# ASCII_10_FPGA_misc.net
KiCad netlist of a schematic drawn in Altium Designer
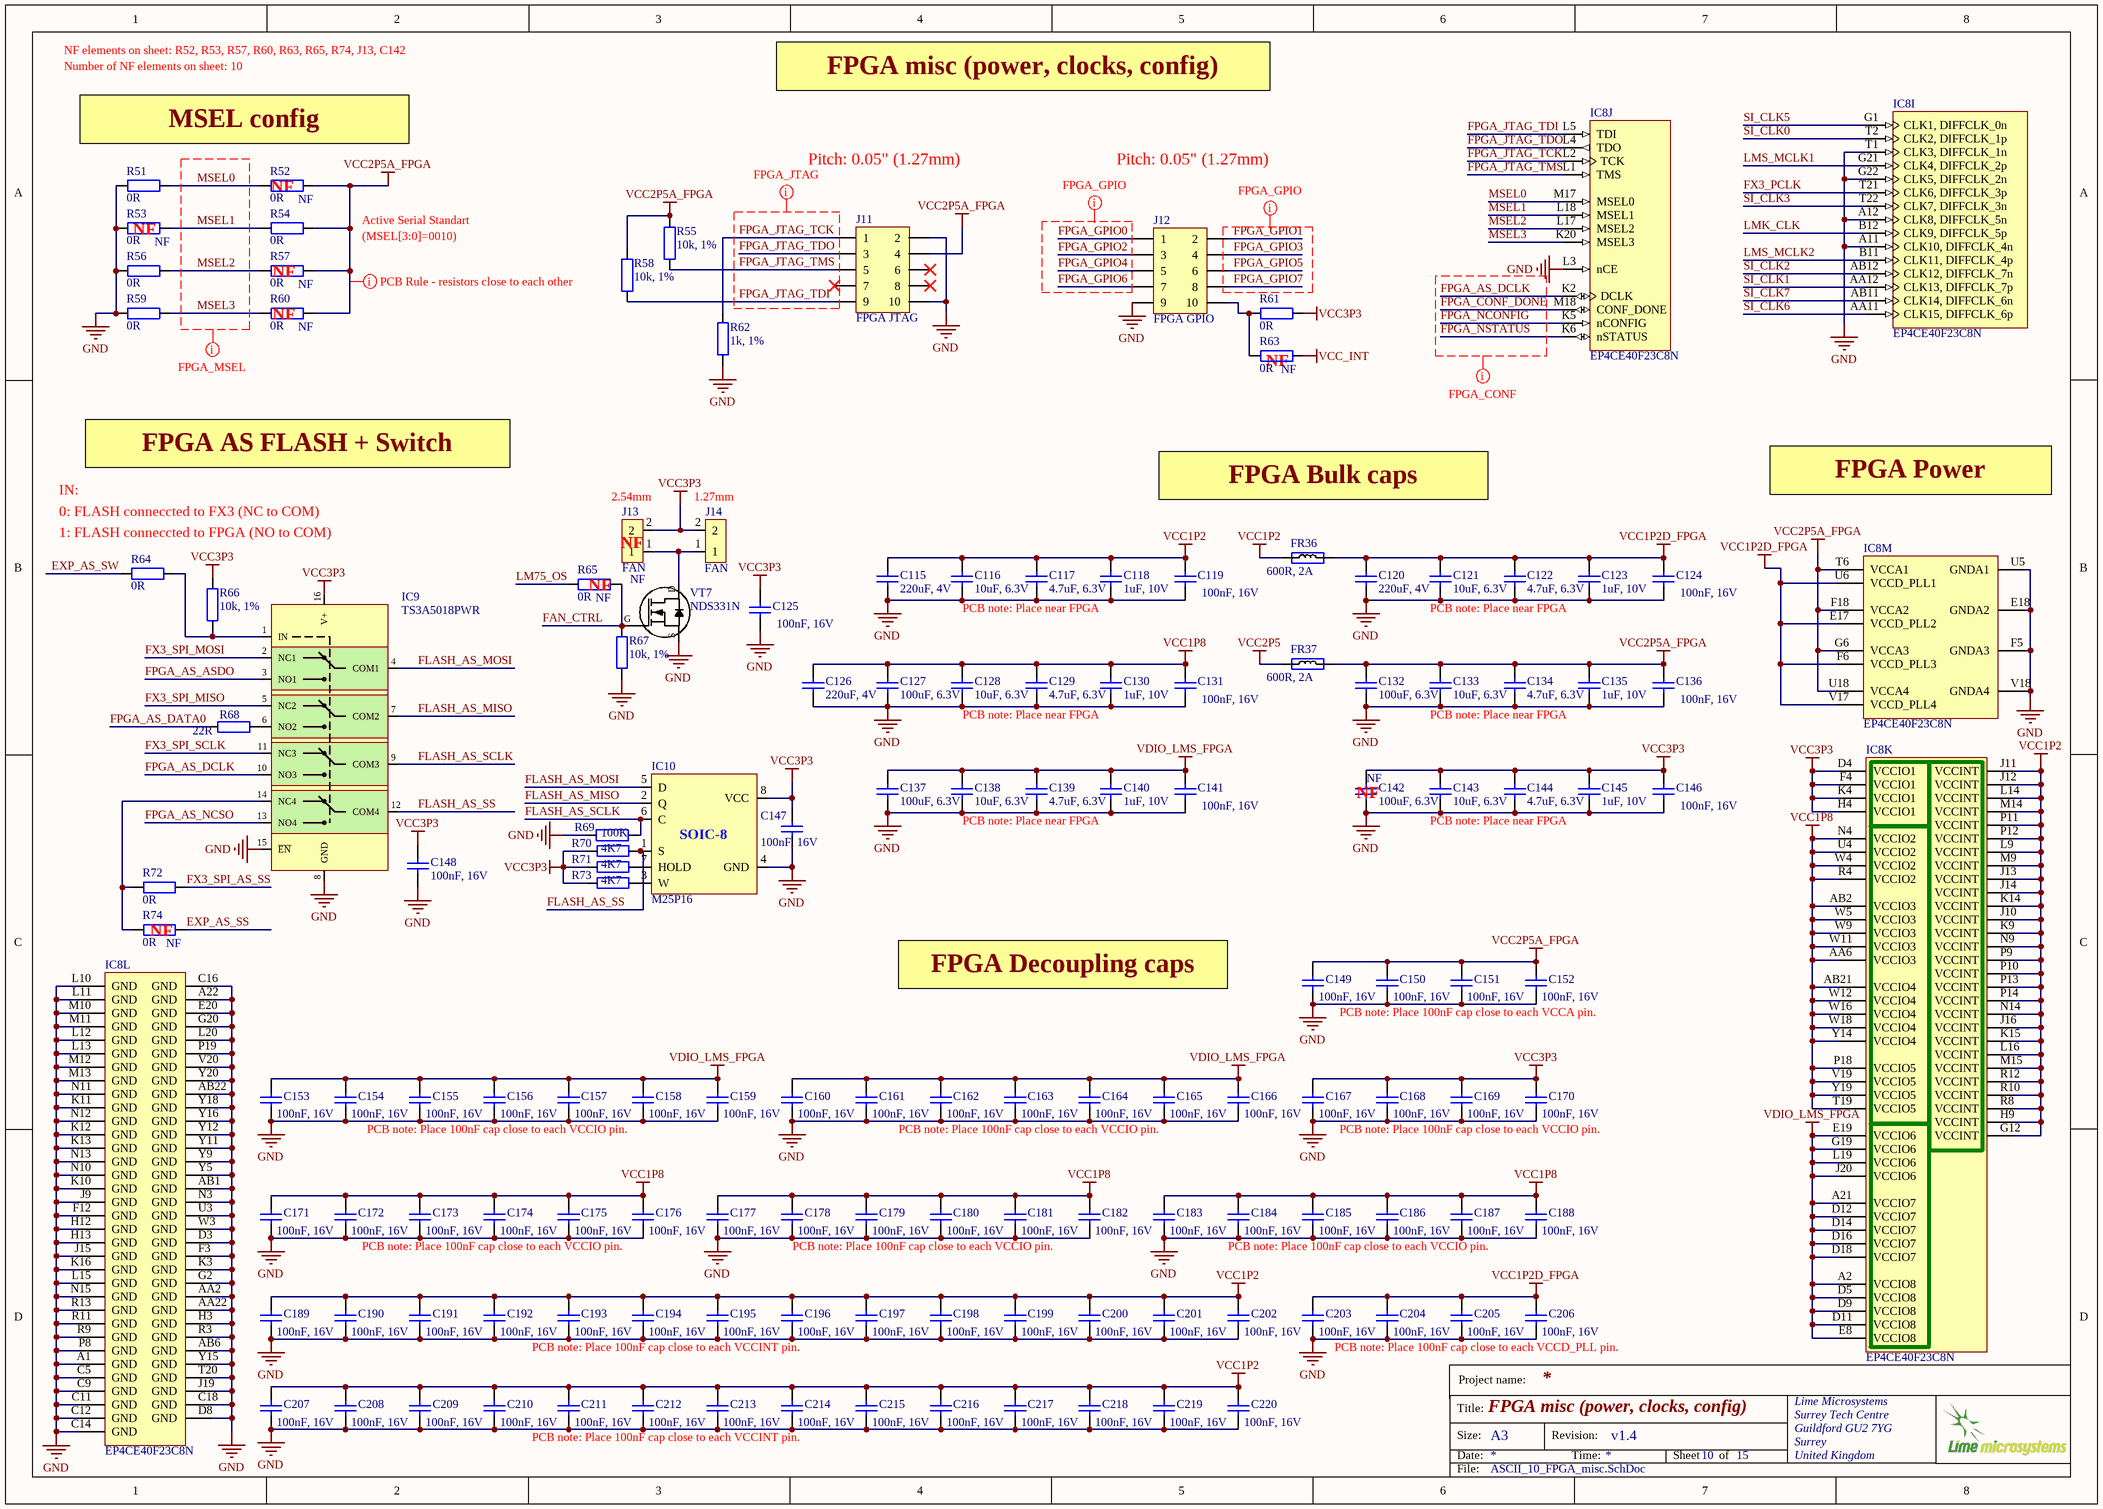
[diagram p0: ASCII_10_FPGA_misc.SchDoc]

(export (version "E")
  (design (tool "Eeschema 10.0.6"))
  (components
    (comp (ref "C115")
      (value "220uF, 4V")
      (footprint "CAP1206")
      (fields
        (field (name "MANUFACTURER PART NUMBER") "GRM31CR60G227ME11L")
        (field (name "MANUFACTURER") "Murata Electronics North America")
        (field (name "TOLERANCE") "±20%")
      )
      (libsource (lib "LimeFPGAboard_schLib") (part "Cap_1206"))
    )
    (comp (ref "C116")
      (value "10uF, 6.3V")
      (footprint "CAP0603")
      (fields (field (name "TOLERANCE") "±20%") (field (name "MANUFACTURER") "Yageo"))
      (libsource (lib "LimeFPGAboard_schLib") (part "Cap_0603"))
    )
    (comp (ref "C117")
      (value "4.7uF, 6.3V")
      (footprint "CAP0402")
      (fields
        (field (name "MANUFACTURER") "Murata Electronics North America")
        (field (name "TOLERANCE") "±20%")
        (field (name "MANUFACTURER PART NUMBER") "GRM155R60J475ME87D")
      )
      (libsource (lib "LimeMicroAltiumLib_schLib") (part "Cap_0402"))
    )
    (comp (ref "C118")
      (value "1uF, 10V")
      (footprint "CAP0402")
      (fields (field (name "MANUFACTURER") "TDK"))
      (libsource (lib "LimeMicroAltiumLib_schLib") (part "Cap_0402"))
    )
    (comp (ref "C119")
      (value "100nF, 16V")
      (footprint "CAP0402")
      (fields
        (field (name "TOLERANCE") "10 %")
        (field (name "MANUFACTURER") "Murata Electronics")
        (field (name "MANUFACTURER PART NUMBER") "GRM155R71C104KA88D")
      )
      (libsource (lib "LimeFPGAboard_schLib") (part "Cap_0603"))
    )
    (comp (ref "C120")
      (value "220uF, 4V")
      (footprint "CAP1206")
      (fields
        (field (name "MANUFACTURER PART NUMBER") "GRM31CR60G227ME11L")
        (field (name "MANUFACTURER") "Murata Electronics North America")
        (field (name "TOLERANCE") "±20%")
      )
      (libsource (lib "LimeFPGAboard_schLib") (part "Cap_1206"))
    )
    (comp (ref "C121")
      (value "10uF, 6.3V")
      (footprint "CAP0603")
      (fields (field (name "TOLERANCE") "±20%") (field (name "MANUFACTURER") "Yageo"))
      (libsource (lib "LimeFPGAboard_schLib") (part "Cap_0603"))
    )
    (comp (ref "C122")
      (value "4.7uF, 6.3V")
      (footprint "CAP0402")
      (fields
        (field (name "MANUFACTURER") "Murata Electronics North America")
        (field (name "TOLERANCE") "±20%")
        (field (name "MANUFACTURER PART NUMBER") "GRM155R60J475ME87D")
      )
      (libsource (lib "LimeMicroAltiumLib_schLib") (part "Cap_0402"))
    )
    (comp (ref "C123")
      (value "1uF, 10V")
      (footprint "CAP0402")
      (fields (field (name "MANUFACTURER") "TDK"))
      (libsource (lib "LimeMicroAltiumLib_schLib") (part "Cap_0402"))
    )
    (comp (ref "C124")
      (value "100nF, 16V")
      (footprint "CAP0402")
      (fields
        (field (name "TOLERANCE") "10 %")
        (field (name "MANUFACTURER") "Murata Electronics")
        (field (name "MANUFACTURER PART NUMBER") "GRM155R71C104KA88D")
      )
      (libsource (lib "LimeFPGAboard_schLib") (part "Cap_0603"))
    )
    (comp (ref "C125")
      (value "100nF, 16V")
      (footprint "CAP0402")
      (fields
        (field (name "TOLERANCE") "10 %")
        (field (name "MANUFACTURER") "Murata Electronics")
        (field (name "MANUFACTURER PART NUMBER") "GRM155R71C104KA88D")
      )
      (libsource (lib "LimeFPGAboard_schLib") (part "Cap_0603"))
    )
    (comp (ref "C126")
      (value "220uF, 4V")
      (footprint "CAP1206")
      (fields
        (field (name "MANUFACTURER PART NUMBER") "GRM31CR60G227ME11L")
        (field (name "MANUFACTURER") "Murata Electronics North America")
        (field (name "TOLERANCE") "±20%")
      )
      (libsource (lib "LimeFPGAboard_schLib") (part "Cap_1206"))
    )
    (comp (ref "C127")
      (value "100uF, 6.3V")
      (footprint "CAP1206")
      (fields (field (name "MANUFACTURER") "Murata Electronics North America"))
      (libsource (lib "LimeFPGAboard_schLib") (part "Cap_1206"))
    )
    (comp (ref "C128")
      (value "10uF, 6.3V")
      (footprint "CAP0603")
      (fields (field (name "TOLERANCE") "±20%") (field (name "MANUFACTURER") "Yageo"))
      (libsource (lib "LimeFPGAboard_schLib") (part "Cap_0603"))
    )
    (comp (ref "C129")
      (value "4.7uF, 6.3V")
      (footprint "CAP0402")
      (fields
        (field (name "MANUFACTURER") "Murata Electronics North America")
        (field (name "TOLERANCE") "±20%")
        (field (name "MANUFACTURER PART NUMBER") "GRM155R60J475ME87D")
      )
      (libsource (lib "LimeMicroAltiumLib_schLib") (part "Cap_0402"))
    )
    (comp (ref "C130")
      (value "1uF, 10V")
      (footprint "CAP0402")
      (fields (field (name "MANUFACTURER") "TDK"))
      (libsource (lib "LimeMicroAltiumLib_schLib") (part "Cap_0402"))
    )
    (comp (ref "C131")
      (value "100nF, 16V")
      (footprint "CAP0402")
      (fields
        (field (name "TOLERANCE") "10 %")
        (field (name "MANUFACTURER") "Murata Electronics")
        (field (name "MANUFACTURER PART NUMBER") "GRM155R71C104KA88D")
      )
      (libsource (lib "LimeFPGAboard_schLib") (part "Cap_0603"))
    )
    (comp (ref "C132")
      (value "100uF, 6.3V")
      (footprint "CAP1206")
      (fields (field (name "MANUFACTURER") "Murata Electronics North America"))
      (libsource (lib "LimeFPGAboard_schLib") (part "Cap_1206"))
    )
    (comp (ref "C133")
      (value "10uF, 6.3V")
      (footprint "CAP0603")
      (fields (field (name "TOLERANCE") "±20%") (field (name "MANUFACTURER") "Yageo"))
      (libsource (lib "LimeFPGAboard_schLib") (part "Cap_0603"))
    )
    (comp (ref "C134")
      (value "4.7uF, 6.3V")
      (footprint "CAP0402")
      (fields
        (field (name "MANUFACTURER") "Murata Electronics North America")
        (field (name "TOLERANCE") "±20%")
        (field (name "MANUFACTURER PART NUMBER") "GRM155R60J475ME87D")
      )
      (libsource (lib "LimeMicroAltiumLib_schLib") (part "Cap_0402"))
    )
    (comp (ref "C135")
      (value "1uF, 10V")
      (footprint "CAP0402")
      (fields (field (name "MANUFACTURER") "TDK"))
      (libsource (lib "LimeMicroAltiumLib_schLib") (part "Cap_0402"))
    )
    (comp (ref "C136")
      (value "100nF, 16V")
      (footprint "CAP0402")
      (fields
        (field (name "TOLERANCE") "10 %")
        (field (name "MANUFACTURER") "Murata Electronics")
        (field (name "MANUFACTURER PART NUMBER") "GRM155R71C104KA88D")
      )
      (libsource (lib "LimeFPGAboard_schLib") (part "Cap_0603"))
    )
    (comp (ref "C137")
      (value "100uF, 6.3V")
      (footprint "CAP1206")
      (fields (field (name "MANUFACTURER") "Murata Electronics North America"))
      (libsource (lib "LimeFPGAboard_schLib") (part "Cap_1206"))
    )
    (comp (ref "C138")
      (value "10uF, 6.3V")
      (footprint "CAP0603")
      (fields (field (name "TOLERANCE") "±20%") (field (name "MANUFACTURER") "Yageo"))
      (libsource (lib "LimeFPGAboard_schLib") (part "Cap_0603"))
    )
    (comp (ref "C139")
      (value "4.7uF, 6.3V")
      (footprint "CAP0402")
      (fields
        (field (name "MANUFACTURER") "Murata Electronics North America")
        (field (name "TOLERANCE") "±20%")
        (field (name "MANUFACTURER PART NUMBER") "GRM155R60J475ME87D")
      )
      (libsource (lib "LimeMicroAltiumLib_schLib") (part "Cap_0402"))
    )
    (comp (ref "C140")
      (value "1uF, 10V")
      (footprint "CAP0402")
      (fields (field (name "MANUFACTURER") "TDK"))
      (libsource (lib "LimeMicroAltiumLib_schLib") (part "Cap_0402"))
    )
    (comp (ref "C141")
      (value "100nF, 16V")
      (footprint "CAP0402")
      (fields
        (field (name "TOLERANCE") "10 %")
        (field (name "MANUFACTURER") "Murata Electronics")
        (field (name "MANUFACTURER PART NUMBER") "GRM155R71C104KA88D")
      )
      (libsource (lib "LimeFPGAboard_schLib") (part "Cap_0603"))
    )
    (comp (ref "C142")
      (value "100uF, 6.3V")
      (footprint "CAP1206")
      (fields
        (field (name "MANUFACTURER") "Murata Electronics North America")
        (field (name "ASSEMBLY INFO") "NF")
      )
      (libsource (lib "LimeFPGAboard_schLib") (part "Cap_1206"))
    )
    (comp (ref "C143")
      (value "10uF, 6.3V")
      (footprint "CAP0603")
      (fields (field (name "TOLERANCE") "±20%") (field (name "MANUFACTURER") "Yageo"))
      (libsource (lib "LimeFPGAboard_schLib") (part "Cap_0603"))
    )
    (comp (ref "C144")
      (value "4.7uF, 6.3V")
      (footprint "CAP0402")
      (fields
        (field (name "MANUFACTURER") "Murata Electronics North America")
        (field (name "TOLERANCE") "±20%")
        (field (name "MANUFACTURER PART NUMBER") "GRM155R60J475ME87D")
      )
      (libsource (lib "LimeMicroAltiumLib_schLib") (part "Cap_0402"))
    )
    (comp (ref "C145")
      (value "1uF, 10V")
      (footprint "CAP0402")
      (fields (field (name "MANUFACTURER") "TDK"))
      (libsource (lib "LimeMicroAltiumLib_schLib") (part "Cap_0402"))
    )
    (comp (ref "C146")
      (value "100nF, 16V")
      (footprint "CAP0402")
      (fields
        (field (name "TOLERANCE") "10 %")
        (field (name "MANUFACTURER") "Murata Electronics")
        (field (name "MANUFACTURER PART NUMBER") "GRM155R71C104KA88D")
      )
      (libsource (lib "LimeFPGAboard_schLib") (part "Cap_0603"))
    )
    (comp (ref "C147")
      (value "100nF, 16V")
      (footprint "CAP0402")
      (fields
        (field (name "TOLERANCE") "10 %")
        (field (name "MANUFACTURER") "Murata Electronics")
        (field (name "MANUFACTURER PART NUMBER") "GRM155R71C104KA88D")
      )
      (libsource (lib "LimeFPGAboard_schLib") (part "Cap_0603"))
    )
    (comp (ref "C148")
      (value "100nF, 16V")
      (footprint "CAP0402")
      (fields
        (field (name "TOLERANCE") "10 %")
        (field (name "MANUFACTURER") "Murata Electronics")
        (field (name "MANUFACTURER PART NUMBER") "GRM155R71C104KA88D")
      )
      (libsource (lib "LimeFPGAboard_schLib") (part "Cap_0603"))
    )
    (comp (ref "C149")
      (value "100nF, 16V")
      (footprint "CAP0402")
      (fields
        (field (name "TOLERANCE") "10 %")
        (field (name "MANUFACTURER") "Murata Electronics")
        (field (name "MANUFACTURER PART NUMBER") "GRM155R71C104KA88D")
      )
      (libsource (lib "LimeFPGAboard_schLib") (part "Cap_0603"))
    )
    (comp (ref "C150")
      (value "100nF, 16V")
      (footprint "CAP0402")
      (fields
        (field (name "TOLERANCE") "10 %")
        (field (name "MANUFACTURER") "Murata Electronics")
        (field (name "MANUFACTURER PART NUMBER") "GRM155R71C104KA88D")
      )
      (libsource (lib "LimeFPGAboard_schLib") (part "Cap_0603"))
    )
    (comp (ref "C151")
      (value "100nF, 16V")
      (footprint "CAP0402")
      (fields
        (field (name "TOLERANCE") "10 %")
        (field (name "MANUFACTURER") "Murata Electronics")
        (field (name "MANUFACTURER PART NUMBER") "GRM155R71C104KA88D")
      )
      (libsource (lib "LimeFPGAboard_schLib") (part "Cap_0603"))
    )
    (comp (ref "C152")
      (value "100nF, 16V")
      (footprint "CAP0402")
      (fields
        (field (name "TOLERANCE") "10 %")
        (field (name "MANUFACTURER") "Murata Electronics")
        (field (name "MANUFACTURER PART NUMBER") "GRM155R71C104KA88D")
      )
      (libsource (lib "LimeFPGAboard_schLib") (part "Cap_0603"))
    )
    (comp (ref "C153")
      (value "100nF, 16V")
      (footprint "CAP0402")
      (fields
        (field (name "TOLERANCE") "10 %")
        (field (name "MANUFACTURER") "Murata Electronics")
        (field (name "MANUFACTURER PART NUMBER") "GRM155R71C104KA88D")
      )
      (libsource (lib "LimeFPGAboard_schLib") (part "Cap_0603"))
    )
    (comp (ref "C154")
      (value "100nF, 16V")
      (footprint "CAP0402")
      (fields
        (field (name "TOLERANCE") "10 %")
        (field (name "MANUFACTURER") "Murata Electronics")
        (field (name "MANUFACTURER PART NUMBER") "GRM155R71C104KA88D")
      )
      (libsource (lib "LimeFPGAboard_schLib") (part "Cap_0603"))
    )
    (comp (ref "C155")
      (value "100nF, 16V")
      (footprint "CAP0402")
      (fields
        (field (name "TOLERANCE") "10 %")
        (field (name "MANUFACTURER") "Murata Electronics")
        (field (name "MANUFACTURER PART NUMBER") "GRM155R71C104KA88D")
      )
      (libsource (lib "LimeFPGAboard_schLib") (part "Cap_0603"))
    )
    (comp (ref "C156")
      (value "100nF, 16V")
      (footprint "CAP0402")
      (fields
        (field (name "TOLERANCE") "10 %")
        (field (name "MANUFACTURER") "Murata Electronics")
        (field (name "MANUFACTURER PART NUMBER") "GRM155R71C104KA88D")
      )
      (libsource (lib "LimeFPGAboard_schLib") (part "Cap_0603"))
    )
    (comp (ref "C157")
      (value "100nF, 16V")
      (footprint "CAP0402")
      (fields
        (field (name "TOLERANCE") "10 %")
        (field (name "MANUFACTURER") "Murata Electronics")
        (field (name "MANUFACTURER PART NUMBER") "GRM155R71C104KA88D")
      )
      (libsource (lib "LimeFPGAboard_schLib") (part "Cap_0603"))
    )
    (comp (ref "C158")
      (value "100nF, 16V")
      (footprint "CAP0402")
      (fields
        (field (name "TOLERANCE") "10 %")
        (field (name "MANUFACTURER") "Murata Electronics")
        (field (name "MANUFACTURER PART NUMBER") "GRM155R71C104KA88D")
      )
      (libsource (lib "LimeFPGAboard_schLib") (part "Cap_0603"))
    )
    (comp (ref "C159")
      (value "100nF, 16V")
      (footprint "CAP0402")
      (fields
        (field (name "TOLERANCE") "10 %")
        (field (name "MANUFACTURER") "Murata Electronics")
        (field (name "MANUFACTURER PART NUMBER") "GRM155R71C104KA88D")
      )
      (libsource (lib "LimeFPGAboard_schLib") (part "Cap_0603"))
    )
    (comp (ref "C160")
      (value "100nF, 16V")
      (footprint "CAP0402")
      (fields
        (field (name "TOLERANCE") "10 %")
        (field (name "MANUFACTURER") "Murata Electronics")
        (field (name "MANUFACTURER PART NUMBER") "GRM155R71C104KA88D")
      )
      (libsource (lib "LimeFPGAboard_schLib") (part "Cap_0603"))
    )
    (comp (ref "C161")
      (value "100nF, 16V")
      (footprint "CAP0402")
      (fields
        (field (name "TOLERANCE") "10 %")
        (field (name "MANUFACTURER") "Murata Electronics")
        (field (name "MANUFACTURER PART NUMBER") "GRM155R71C104KA88D")
      )
      (libsource (lib "LimeFPGAboard_schLib") (part "Cap_0603"))
    )
    (comp (ref "C162")
      (value "100nF, 16V")
      (footprint "CAP0402")
      (fields
        (field (name "TOLERANCE") "10 %")
        (field (name "MANUFACTURER") "Murata Electronics")
        (field (name "MANUFACTURER PART NUMBER") "GRM155R71C104KA88D")
      )
      (libsource (lib "LimeFPGAboard_schLib") (part "Cap_0603"))
    )
    (comp (ref "C163")
      (value "100nF, 16V")
      (footprint "CAP0402")
      (fields
        (field (name "TOLERANCE") "10 %")
        (field (name "MANUFACTURER") "Murata Electronics")
        (field (name "MANUFACTURER PART NUMBER") "GRM155R71C104KA88D")
      )
      (libsource (lib "LimeFPGAboard_schLib") (part "Cap_0603"))
    )
    (comp (ref "C164")
      (value "100nF, 16V")
      (footprint "CAP0402")
      (fields
        (field (name "TOLERANCE") "10 %")
        (field (name "MANUFACTURER") "Murata Electronics")
        (field (name "MANUFACTURER PART NUMBER") "GRM155R71C104KA88D")
      )
      (libsource (lib "LimeFPGAboard_schLib") (part "Cap_0603"))
    )
    (comp (ref "C165")
      (value "100nF, 16V")
      (footprint "CAP0402")
      (fields
        (field (name "TOLERANCE") "10 %")
        (field (name "MANUFACTURER") "Murata Electronics")
        (field (name "MANUFACTURER PART NUMBER") "GRM155R71C104KA88D")
      )
      (libsource (lib "LimeFPGAboard_schLib") (part "Cap_0603"))
    )
    (comp (ref "C166")
      (value "100nF, 16V")
      (footprint "CAP0402")
      (fields
        (field (name "TOLERANCE") "10 %")
        (field (name "MANUFACTURER") "Murata Electronics")
        (field (name "MANUFACTURER PART NUMBER") "GRM155R71C104KA88D")
      )
      (libsource (lib "LimeFPGAboard_schLib") (part "Cap_0603"))
    )
    (comp (ref "C167")
      (value "100nF, 16V")
      (footprint "CAP0402")
      (fields
        (field (name "TOLERANCE") "10 %")
        (field (name "MANUFACTURER") "Murata Electronics")
        (field (name "MANUFACTURER PART NUMBER") "GRM155R71C104KA88D")
      )
      (libsource (lib "LimeFPGAboard_schLib") (part "Cap_0603"))
    )
    (comp (ref "C168")
      (value "100nF, 16V")
      (footprint "CAP0402")
      (fields
        (field (name "TOLERANCE") "10 %")
        (field (name "MANUFACTURER") "Murata Electronics")
        (field (name "MANUFACTURER PART NUMBER") "GRM155R71C104KA88D")
      )
      (libsource (lib "LimeFPGAboard_schLib") (part "Cap_0603"))
    )
    (comp (ref "C169")
      (value "100nF, 16V")
      (footprint "CAP0402")
      (fields
        (field (name "TOLERANCE") "10 %")
        (field (name "MANUFACTURER") "Murata Electronics")
        (field (name "MANUFACTURER PART NUMBER") "GRM155R71C104KA88D")
      )
      (libsource (lib "LimeFPGAboard_schLib") (part "Cap_0603"))
    )
    (comp (ref "C170")
      (value "100nF, 16V")
      (footprint "CAP0402")
      (fields
        (field (name "TOLERANCE") "10 %")
        (field (name "MANUFACTURER") "Murata Electronics")
        (field (name "MANUFACTURER PART NUMBER") "GRM155R71C104KA88D")
      )
      (libsource (lib "LimeFPGAboard_schLib") (part "Cap_0603"))
    )
    (comp (ref "C171")
      (value "100nF, 16V")
      (footprint "CAP0402")
      (fields
        (field (name "TOLERANCE") "10 %")
        (field (name "MANUFACTURER") "Murata Electronics")
        (field (name "MANUFACTURER PART NUMBER") "GRM155R71C104KA88D")
      )
      (libsource (lib "LimeFPGAboard_schLib") (part "Cap_0603"))
    )
    (comp (ref "C172")
      (value "100nF, 16V")
      (footprint "CAP0402")
      (fields
        (field (name "TOLERANCE") "10 %")
        (field (name "MANUFACTURER") "Murata Electronics")
        (field (name "MANUFACTURER PART NUMBER") "GRM155R71C104KA88D")
      )
      (libsource (lib "LimeFPGAboard_schLib") (part "Cap_0603"))
    )
    (comp (ref "C173")
      (value "100nF, 16V")
      (footprint "CAP0402")
      (fields
        (field (name "TOLERANCE") "10 %")
        (field (name "MANUFACTURER") "Murata Electronics")
        (field (name "MANUFACTURER PART NUMBER") "GRM155R71C104KA88D")
      )
      (libsource (lib "LimeFPGAboard_schLib") (part "Cap_0603"))
    )
    (comp (ref "C174")
      (value "100nF, 16V")
      (footprint "CAP0402")
      (fields
        (field (name "TOLERANCE") "10 %")
        (field (name "MANUFACTURER") "Murata Electronics")
        (field (name "MANUFACTURER PART NUMBER") "GRM155R71C104KA88D")
      )
      (libsource (lib "LimeFPGAboard_schLib") (part "Cap_0603"))
    )
    (comp (ref "C175")
      (value "100nF, 16V")
      (footprint "CAP0402")
      (fields
        (field (name "TOLERANCE") "10 %")
        (field (name "MANUFACTURER") "Murata Electronics")
        (field (name "MANUFACTURER PART NUMBER") "GRM155R71C104KA88D")
      )
      (libsource (lib "LimeFPGAboard_schLib") (part "Cap_0603"))
    )
    (comp (ref "C176")
      (value "100nF, 16V")
      (footprint "CAP0402")
      (fields
        (field (name "TOLERANCE") "10 %")
        (field (name "MANUFACTURER") "Murata Electronics")
        (field (name "MANUFACTURER PART NUMBER") "GRM155R71C104KA88D")
      )
      (libsource (lib "LimeFPGAboard_schLib") (part "Cap_0603"))
    )
    (comp (ref "C177")
      (value "100nF, 16V")
      (footprint "CAP0402")
      (fields
        (field (name "TOLERANCE") "10 %")
        (field (name "MANUFACTURER") "Murata Electronics")
        (field (name "MANUFACTURER PART NUMBER") "GRM155R71C104KA88D")
      )
      (libsource (lib "LimeFPGAboard_schLib") (part "Cap_0603"))
    )
    (comp (ref "C178")
      (value "100nF, 16V")
      (footprint "CAP0402")
      (fields
        (field (name "TOLERANCE") "10 %")
        (field (name "MANUFACTURER") "Murata Electronics")
        (field (name "MANUFACTURER PART NUMBER") "GRM155R71C104KA88D")
      )
      (libsource (lib "LimeFPGAboard_schLib") (part "Cap_0603"))
    )
    (comp (ref "C179")
      (value "100nF, 16V")
      (footprint "CAP0402")
      (fields
        (field (name "TOLERANCE") "10 %")
        (field (name "MANUFACTURER") "Murata Electronics")
        (field (name "MANUFACTURER PART NUMBER") "GRM155R71C104KA88D")
      )
      (libsource (lib "LimeFPGAboard_schLib") (part "Cap_0603"))
    )
    (comp (ref "C180")
      (value "100nF, 16V")
      (footprint "CAP0402")
      (fields
        (field (name "TOLERANCE") "10 %")
        (field (name "MANUFACTURER") "Murata Electronics")
        (field (name "MANUFACTURER PART NUMBER") "GRM155R71C104KA88D")
      )
      (libsource (lib "LimeFPGAboard_schLib") (part "Cap_0603"))
    )
    (comp (ref "C181")
      (value "100nF, 16V")
      (footprint "CAP0402")
      (fields
        (field (name "TOLERANCE") "10 %")
        (field (name "MANUFACTURER") "Murata Electronics")
        (field (name "MANUFACTURER PART NUMBER") "GRM155R71C104KA88D")
      )
      (libsource (lib "LimeFPGAboard_schLib") (part "Cap_0603"))
    )
    (comp (ref "C182")
      (value "100nF, 16V")
      (footprint "CAP0402")
      (fields
        (field (name "TOLERANCE") "10 %")
        (field (name "MANUFACTURER") "Murata Electronics")
        (field (name "MANUFACTURER PART NUMBER") "GRM155R71C104KA88D")
      )
      (libsource (lib "LimeFPGAboard_schLib") (part "Cap_0603"))
    )
    (comp (ref "C183")
      (value "100nF, 16V")
      (footprint "CAP0402")
      (fields
        (field (name "TOLERANCE") "10 %")
        (field (name "MANUFACTURER") "Murata Electronics")
        (field (name "MANUFACTURER PART NUMBER") "GRM155R71C104KA88D")
      )
      (libsource (lib "LimeFPGAboard_schLib") (part "Cap_0603"))
    )
    (comp (ref "C184")
      (value "100nF, 16V")
      (footprint "CAP0402")
      (fields
        (field (name "TOLERANCE") "10 %")
        (field (name "MANUFACTURER") "Murata Electronics")
        (field (name "MANUFACTURER PART NUMBER") "GRM155R71C104KA88D")
      )
      (libsource (lib "LimeFPGAboard_schLib") (part "Cap_0603"))
    )
    (comp (ref "C185")
      (value "100nF, 16V")
      (footprint "CAP0402")
      (fields
        (field (name "TOLERANCE") "10 %")
        (field (name "MANUFACTURER") "Murata Electronics")
        (field (name "MANUFACTURER PART NUMBER") "GRM155R71C104KA88D")
      )
      (libsource (lib "LimeFPGAboard_schLib") (part "Cap_0603"))
    )
    (comp (ref "C186")
      (value "100nF, 16V")
      (footprint "CAP0402")
      (fields
        (field (name "TOLERANCE") "10 %")
        (field (name "MANUFACTURER") "Murata Electronics")
        (field (name "MANUFACTURER PART NUMBER") "GRM155R71C104KA88D")
      )
      (libsource (lib "LimeFPGAboard_schLib") (part "Cap_0603"))
    )
    (comp (ref "C187")
      (value "100nF, 16V")
      (footprint "CAP0402")
      (fields
        (field (name "TOLERANCE") "10 %")
        (field (name "MANUFACTURER") "Murata Electronics")
        (field (name "MANUFACTURER PART NUMBER") "GRM155R71C104KA88D")
      )
      (libsource (lib "LimeFPGAboard_schLib") (part "Cap_0603"))
    )
    (comp (ref "C188")
      (value "100nF, 16V")
      (footprint "CAP0402")
      (fields
        (field (name "TOLERANCE") "10 %")
        (field (name "MANUFACTURER") "Murata Electronics")
        (field (name "MANUFACTURER PART NUMBER") "GRM155R71C104KA88D")
      )
      (libsource (lib "LimeFPGAboard_schLib") (part "Cap_0603"))
    )
    (comp (ref "C189")
      (value "100nF, 16V")
      (footprint "CAP0402")
      (fields
        (field (name "TOLERANCE") "10 %")
        (field (name "MANUFACTURER") "Murata Electronics")
        (field (name "MANUFACTURER PART NUMBER") "GRM155R71C104KA88D")
      )
      (libsource (lib "LimeFPGAboard_schLib") (part "Cap_0603"))
    )
    (comp (ref "C190")
      (value "100nF, 16V")
      (footprint "CAP0402")
      (fields
        (field (name "TOLERANCE") "10 %")
        (field (name "MANUFACTURER") "Murata Electronics")
        (field (name "MANUFACTURER PART NUMBER") "GRM155R71C104KA88D")
      )
      (libsource (lib "LimeFPGAboard_schLib") (part "Cap_0603"))
    )
    (comp (ref "C191")
      (value "100nF, 16V")
      (footprint "CAP0402")
      (fields
        (field (name "TOLERANCE") "10 %")
        (field (name "MANUFACTURER") "Murata Electronics")
        (field (name "MANUFACTURER PART NUMBER") "GRM155R71C104KA88D")
      )
      (libsource (lib "LimeFPGAboard_schLib") (part "Cap_0603"))
    )
    (comp (ref "C192")
      (value "100nF, 16V")
      (footprint "CAP0402")
      (fields
        (field (name "TOLERANCE") "10 %")
        (field (name "MANUFACTURER") "Murata Electronics")
        (field (name "MANUFACTURER PART NUMBER") "GRM155R71C104KA88D")
      )
      (libsource (lib "LimeFPGAboard_schLib") (part "Cap_0603"))
    )
    (comp (ref "C193")
      (value "100nF, 16V")
      (footprint "CAP0402")
      (fields
        (field (name "TOLERANCE") "10 %")
        (field (name "MANUFACTURER") "Murata Electronics")
        (field (name "MANUFACTURER PART NUMBER") "GRM155R71C104KA88D")
      )
      (libsource (lib "LimeFPGAboard_schLib") (part "Cap_0603"))
    )
    (comp (ref "C194")
      (value "100nF, 16V")
      (footprint "CAP0402")
      (fields
        (field (name "TOLERANCE") "10 %")
        (field (name "MANUFACTURER") "Murata Electronics")
        (field (name "MANUFACTURER PART NUMBER") "GRM155R71C104KA88D")
      )
      (libsource (lib "LimeFPGAboard_schLib") (part "Cap_0603"))
    )
    (comp (ref "C195")
      (value "100nF, 16V")
      (footprint "CAP0402")
      (fields
        (field (name "TOLERANCE") "10 %")
        (field (name "MANUFACTURER") "Murata Electronics")
        (field (name "MANUFACTURER PART NUMBER") "GRM155R71C104KA88D")
      )
      (libsource (lib "LimeFPGAboard_schLib") (part "Cap_0603"))
    )
    (comp (ref "C196")
      (value "100nF, 16V")
      (footprint "CAP0402")
      (fields
        (field (name "TOLERANCE") "10 %")
        (field (name "MANUFACTURER") "Murata Electronics")
        (field (name "MANUFACTURER PART NUMBER") "GRM155R71C104KA88D")
      )
      (libsource (lib "LimeFPGAboard_schLib") (part "Cap_0603"))
    )
    (comp (ref "C197")
      (value "100nF, 16V")
      (footprint "CAP0402")
      (fields
        (field (name "TOLERANCE") "10 %")
        (field (name "MANUFACTURER") "Murata Electronics")
        (field (name "MANUFACTURER PART NUMBER") "GRM155R71C104KA88D")
      )
      (libsource (lib "LimeFPGAboard_schLib") (part "Cap_0603"))
    )
    (comp (ref "C198")
      (value "100nF, 16V")
      (footprint "CAP0402")
      (fields
        (field (name "TOLERANCE") "10 %")
        (field (name "MANUFACTURER") "Murata Electronics")
        (field (name "MANUFACTURER PART NUMBER") "GRM155R71C104KA88D")
      )
      (libsource (lib "LimeFPGAboard_schLib") (part "Cap_0603"))
    )
    (comp (ref "C199")
      (value "100nF, 16V")
      (footprint "CAP0402")
      (fields
        (field (name "TOLERANCE") "10 %")
        (field (name "MANUFACTURER") "Murata Electronics")
        (field (name "MANUFACTURER PART NUMBER") "GRM155R71C104KA88D")
      )
      (libsource (lib "LimeFPGAboard_schLib") (part "Cap_0603"))
    )
    (comp (ref "C200")
      (value "100nF, 16V")
      (footprint "CAP0402")
      (fields
        (field (name "TOLERANCE") "10 %")
        (field (name "MANUFACTURER") "Murata Electronics")
        (field (name "MANUFACTURER PART NUMBER") "GRM155R71C104KA88D")
      )
      (libsource (lib "LimeFPGAboard_schLib") (part "Cap_0603"))
    )
    (comp (ref "C201")
      (value "100nF, 16V")
      (footprint "CAP0402")
      (fields
        (field (name "TOLERANCE") "10 %")
        (field (name "MANUFACTURER") "Murata Electronics")
        (field (name "MANUFACTURER PART NUMBER") "GRM155R71C104KA88D")
      )
      (libsource (lib "LimeFPGAboard_schLib") (part "Cap_0603"))
    )
    (comp (ref "C202")
      (value "100nF, 16V")
      (footprint "CAP0402")
      (fields
        (field (name "TOLERANCE") "10 %")
        (field (name "MANUFACTURER") "Murata Electronics")
        (field (name "MANUFACTURER PART NUMBER") "GRM155R71C104KA88D")
      )
      (libsource (lib "LimeFPGAboard_schLib") (part "Cap_0603"))
    )
    (comp (ref "C203")
      (value "100nF, 16V")
      (footprint "CAP0402")
      (fields
        (field (name "TOLERANCE") "10 %")
        (field (name "MANUFACTURER") "Murata Electronics")
        (field (name "MANUFACTURER PART NUMBER") "GRM155R71C104KA88D")
      )
      (libsource (lib "LimeFPGAboard_schLib") (part "Cap_0603"))
    )
    (comp (ref "C204")
      (value "100nF, 16V")
      (footprint "CAP0402")
      (fields
        (field (name "TOLERANCE") "10 %")
        (field (name "MANUFACTURER") "Murata Electronics")
        (field (name "MANUFACTURER PART NUMBER") "GRM155R71C104KA88D")
      )
      (libsource (lib "LimeFPGAboard_schLib") (part "Cap_0603"))
    )
    (comp (ref "C205")
      (value "100nF, 16V")
      (footprint "CAP0402")
      (fields
        (field (name "TOLERANCE") "10 %")
        (field (name "MANUFACTURER") "Murata Electronics")
        (field (name "MANUFACTURER PART NUMBER") "GRM155R71C104KA88D")
      )
      (libsource (lib "LimeFPGAboard_schLib") (part "Cap_0603"))
    )
    (comp (ref "C206")
      (value "100nF, 16V")
      (footprint "CAP0402")
      (fields
        (field (name "TOLERANCE") "10 %")
        (field (name "MANUFACTURER") "Murata Electronics")
        (field (name "MANUFACTURER PART NUMBER") "GRM155R71C104KA88D")
      )
      (libsource (lib "LimeFPGAboard_schLib") (part "Cap_0603"))
    )
    (comp (ref "C207")
      (value "100nF, 16V")
      (footprint "CAP0402")
      (fields
        (field (name "TOLERANCE") "10 %")
        (field (name "MANUFACTURER") "Murata Electronics")
        (field (name "MANUFACTURER PART NUMBER") "GRM155R71C104KA88D")
      )
      (libsource (lib "LimeFPGAboard_schLib") (part "Cap_0603"))
    )
    (comp (ref "C208")
      (value "100nF, 16V")
      (footprint "CAP0402")
      (fields
        (field (name "TOLERANCE") "10 %")
        (field (name "MANUFACTURER") "Murata Electronics")
        (field (name "MANUFACTURER PART NUMBER") "GRM155R71C104KA88D")
      )
      (libsource (lib "LimeFPGAboard_schLib") (part "Cap_0603"))
    )
    (comp (ref "C209")
      (value "100nF, 16V")
      (footprint "CAP0402")
      (fields
        (field (name "TOLERANCE") "10 %")
        (field (name "MANUFACTURER") "Murata Electronics")
        (field (name "MANUFACTURER PART NUMBER") "GRM155R71C104KA88D")
      )
      (libsource (lib "LimeFPGAboard_schLib") (part "Cap_0603"))
    )
    (comp (ref "C210")
      (value "100nF, 16V")
      (footprint "CAP0402")
      (fields
        (field (name "TOLERANCE") "10 %")
        (field (name "MANUFACTURER") "Murata Electronics")
        (field (name "MANUFACTURER PART NUMBER") "GRM155R71C104KA88D")
      )
      (libsource (lib "LimeFPGAboard_schLib") (part "Cap_0603"))
    )
    (comp (ref "C211")
      (value "100nF, 16V")
      (footprint "CAP0402")
      (fields
        (field (name "TOLERANCE") "10 %")
        (field (name "MANUFACTURER") "Murata Electronics")
        (field (name "MANUFACTURER PART NUMBER") "GRM155R71C104KA88D")
      )
      (libsource (lib "LimeFPGAboard_schLib") (part "Cap_0603"))
    )
    (comp (ref "C212")
      (value "100nF, 16V")
      (footprint "CAP0402")
      (fields
        (field (name "TOLERANCE") "10 %")
        (field (name "MANUFACTURER") "Murata Electronics")
        (field (name "MANUFACTURER PART NUMBER") "GRM155R71C104KA88D")
      )
      (libsource (lib "LimeFPGAboard_schLib") (part "Cap_0603"))
    )
    (comp (ref "C213")
      (value "100nF, 16V")
      (footprint "CAP0402")
      (fields
        (field (name "TOLERANCE") "10 %")
        (field (name "MANUFACTURER") "Murata Electronics")
        (field (name "MANUFACTURER PART NUMBER") "GRM155R71C104KA88D")
      )
      (libsource (lib "LimeFPGAboard_schLib") (part "Cap_0603"))
    )
    (comp (ref "C214")
      (value "100nF, 16V")
      (footprint "CAP0402")
      (fields
        (field (name "TOLERANCE") "10 %")
        (field (name "MANUFACTURER") "Murata Electronics")
        (field (name "MANUFACTURER PART NUMBER") "GRM155R71C104KA88D")
      )
      (libsource (lib "LimeFPGAboard_schLib") (part "Cap_0603"))
    )
    (comp (ref "C215")
      (value "100nF, 16V")
      (footprint "CAP0402")
      (fields
        (field (name "TOLERANCE") "10 %")
        (field (name "MANUFACTURER") "Murata Electronics")
        (field (name "MANUFACTURER PART NUMBER") "GRM155R71C104KA88D")
      )
      (libsource (lib "LimeFPGAboard_schLib") (part "Cap_0603"))
    )
    (comp (ref "C216")
      (value "100nF, 16V")
      (footprint "CAP0402")
      (fields
        (field (name "TOLERANCE") "10 %")
        (field (name "MANUFACTURER") "Murata Electronics")
        (field (name "MANUFACTURER PART NUMBER") "GRM155R71C104KA88D")
      )
      (libsource (lib "LimeFPGAboard_schLib") (part "Cap_0603"))
    )
    (comp (ref "C217")
      (value "100nF, 16V")
      (footprint "CAP0402")
      (fields
        (field (name "TOLERANCE") "10 %")
        (field (name "MANUFACTURER") "Murata Electronics")
        (field (name "MANUFACTURER PART NUMBER") "GRM155R71C104KA88D")
      )
      (libsource (lib "LimeFPGAboard_schLib") (part "Cap_0603"))
    )
    (comp (ref "C218")
      (value "100nF, 16V")
      (footprint "CAP0402")
      (fields
        (field (name "TOLERANCE") "10 %")
        (field (name "MANUFACTURER") "Murata Electronics")
        (field (name "MANUFACTURER PART NUMBER") "GRM155R71C104KA88D")
      )
      (libsource (lib "LimeFPGAboard_schLib") (part "Cap_0603"))
    )
    (comp (ref "C219")
      (value "100nF, 16V")
      (footprint "CAP0402")
      (fields
        (field (name "TOLERANCE") "10 %")
        (field (name "MANUFACTURER") "Murata Electronics")
        (field (name "MANUFACTURER PART NUMBER") "GRM155R71C104KA88D")
      )
      (libsource (lib "LimeFPGAboard_schLib") (part "Cap_0603"))
    )
    (comp (ref "C220")
      (value "100nF, 16V")
      (footprint "CAP0402")
      (fields
        (field (name "TOLERANCE") "10 %")
        (field (name "MANUFACTURER") "Murata Electronics")
        (field (name "MANUFACTURER PART NUMBER") "GRM155R71C104KA88D")
      )
      (libsource (lib "LimeFPGAboard_schLib") (part "Cap_0603"))
    )
    (comp (ref "FR36")
      (value "600R, 2A")
      (footprint "RES0805")
      (fields (field (name "MANUFACTURER") "TDK Corporation"))
      (libsource (lib "LimeMicroAltiumLib_schLib") (part "Ferrite"))
    )
    (comp (ref "FR37")
      (value "600R, 2A")
      (footprint "RES0805")
      (fields (field (name "MANUFACTURER") "TDK Corporation"))
      (libsource (lib "LimeMicroAltiumLib_schLib") (part "Ferrite"))
    )
    (comp (ref "IC8")
      (value "EP4CE40F23C8N")
      (footprint "FBGA484_A-240")
      (description "IC FPGA 328 I/O 484FBGA")
      (fields (field (name "MANUFACTURER") "Altera"))
      (libsource (lib "LimeMicroAltiumLib_schLib") (part "EP4CE40F23C7N"))
    )
    (comp (ref "IC9")
      (value "TS3A5018PWR")
      (footprint "TS3A5018PWR")
      (fields (field (name "MANUFACTURER") "TEXAS INSTRUMENTS"))
      (libsource (lib "LimeFPGAboard_schLib") (part "TS3A5018PWR"))
    )
    (comp (ref "IC10")
      (value "M25P16")
      (footprint "M25P40-VMN6TPB_SO8N")
      (fields (field (name "MANUFACTURER") "Micron Technology Inc."))
      (libsource (lib "LimeFPGAboard_schLib") (part "M25P40"))
    )
    (comp (ref "J11")
      (value "FPGA JTAG")
      (footprint "SWD_10_pin")
      (description "Header, 5-Pin, Dual row")
      (fields (field (name "MANUFACTURER") "Harwin Inc"))
      (libsource (lib "LimeMicroAltiumLib_schLib") (part "Header 5X2_SWD"))
    )
    (comp (ref "J12")
      (value "FPGA GPIO")
      (footprint "SWD_10_pin")
      (description "Header, 5-Pin, Dual row")
      (fields (field (name "MANUFACTURER") "Harwin Inc"))
      (libsource (lib "LimeMicroAltiumLib_schLib") (part "Header 5X2_SWD"))
    )
    (comp (ref "J13")
      (value "FAN")
      (footprint "HDR_1x2")
      (fields (field (name "ASSEMBLY INFO") "NF") (field (name "MANUFACTURER") "3M"))
      (libsource (lib "") (part "Jumper_1"))
    )
    (comp (ref "J14")
      (value "FAN")
      (footprint "HDR_1x2_HALF_PITCH")
      (fields (field (name "MANUFACTURER") "Sullins Connector Solutions"))
      (libsource (lib "LimeFPGAboard_schLib") (part "Jumper"))
    )
    (comp (ref "R51")
      (value "0R")
      (footprint "RES0402")
      (fields (field (name "MANUFACTURER") "Yageo"))
      (libsource (lib "LimeFPGAboard_schLib") (part "Res_0402"))
    )
    (comp (ref "R52")
      (value "0R")
      (footprint "RES0402")
      (fields (field (name "MANUFACTURER") "Yageo") (field (name "ASSEMBLY INFO") "NF"))
      (libsource (lib "LimeFPGAboard_schLib") (part "Res_0402"))
    )
    (comp (ref "R53")
      (value "0R")
      (footprint "RES0402")
      (fields (field (name "MANUFACTURER") "Yageo") (field (name "ASSEMBLY INFO") "NF"))
      (libsource (lib "LimeFPGAboard_schLib") (part "Res_0402"))
    )
    (comp (ref "R54")
      (value "0R")
      (footprint "RES0402")
      (fields (field (name "MANUFACTURER") "Yageo"))
      (libsource (lib "LimeFPGAboard_schLib") (part "Res_0402"))
    )
    (comp (ref "R55")
      (value "10k, 1%")
      (footprint "RES0402")
      (fields (field (name "MANUFACTURER") "Yageo") (field (name "TOLERANCE") "±1%"))
      (libsource (lib "LimeMicroAltiumLib_schLib") (part "Res_0402"))
    )
    (comp (ref "R56")
      (value "0R")
      (footprint "RES0402")
      (fields (field (name "MANUFACTURER") "Yageo"))
      (libsource (lib "LimeFPGAboard_schLib") (part "Res_0402"))
    )
    (comp (ref "R57")
      (value "0R")
      (footprint "RES0402")
      (fields (field (name "MANUFACTURER") "Yageo") (field (name "ASSEMBLY INFO") "NF"))
      (libsource (lib "LimeFPGAboard_schLib") (part "Res_0402"))
    )
    (comp (ref "R58")
      (value "10k, 1%")
      (footprint "RES0402")
      (fields (field (name "MANUFACTURER") "Yageo") (field (name "TOLERANCE") "±1%"))
      (libsource (lib "LimeMicroAltiumLib_schLib") (part "Res_0402"))
    )
    (comp (ref "R59")
      (value "0R")
      (footprint "RES0402")
      (fields (field (name "MANUFACTURER") "Yageo"))
      (libsource (lib "LimeFPGAboard_schLib") (part "Res_0402"))
    )
    (comp (ref "R60")
      (value "0R")
      (footprint "RES0402")
      (fields (field (name "MANUFACTURER") "Yageo") (field (name "ASSEMBLY INFO") "NF"))
      (libsource (lib "LimeFPGAboard_schLib") (part "Res_0402"))
    )
    (comp (ref "R61")
      (value "0R")
      (footprint "RES0402")
      (fields (field (name "MANUFACTURER") "Yageo"))
      (libsource (lib "LimeFPGAboard_schLib") (part "Res_0402"))
    )
    (comp (ref "R62")
      (value "1k, 1%")
      (footprint "RES0402")
      (fields (field (name "MANUFACTURER") "Stackpole Electronics Inc") (field (name "TOLERANCE") "±1%"))
      (libsource (lib "LimeMicroAltiumLib_schLib") (part "Res_0402"))
    )
    (comp (ref "R63")
      (value "0R")
      (footprint "RES0402")
      (fields (field (name "MANUFACTURER") "Yageo") (field (name "ASSEMBLY INFO") "NF"))
      (libsource (lib "LimeFPGAboard_schLib") (part "Res_0402"))
    )
    (comp (ref "R64")
      (value "0R")
      (footprint "RES0402")
      (fields (field (name "MANUFACTURER") "Yageo"))
      (libsource (lib "LimeFPGAboard_schLib") (part "Res_0402"))
    )
    (comp (ref "R65")
      (value "0R")
      (footprint "RES0402")
      (fields (field (name "MANUFACTURER") "Yageo") (field (name "ASSEMBLY INFO") "NF"))
      (libsource (lib "LimeFPGAboard_schLib") (part "Res_0402"))
    )
    (comp (ref "R66")
      (value "10k, 1%")
      (footprint "RES0402")
      (fields (field (name "MANUFACTURER") "Yageo") (field (name "TOLERANCE") "±1%"))
      (libsource (lib "LimeMicroAltiumLib_schLib") (part "Res_0402"))
    )
    (comp (ref "R67")
      (value "10k, 1%")
      (footprint "RES0402")
      (fields (field (name "MANUFACTURER") "Yageo") (field (name "TOLERANCE") "±1%"))
      (libsource (lib "LimeMicroAltiumLib_schLib") (part "Res_0402"))
    )
    (comp (ref "R68")
      (value "22R")
      (footprint "RES0402")
      (fields (field (name "TOLERANCE") "±1%") (field (name "MANUFACTURER") "Yageo"))
      (libsource (lib "LimeFPGAboard_schLib") (part "Res_0402"))
    )
    (comp (ref "R69")
      (value "100K")
      (footprint "RES0402")
      (fields
        (field (name "TOLERANCE") "±5%")
        (field (name "MANUFACTURER") "Panasonic Electronic Components")
      )
      (libsource (lib "LimeFPGAboard_schLib") (part "Res_0402"))
    )
    (comp (ref "R70")
      (value "4K7")
      (footprint "RES0402")
      (fields (field (name "TOLERANCE") "±5%") (field (name "MANUFACTURER") "Stackpole Electronics Inc."))
      (libsource (lib "LimeFPGAboard_schLib") (part "Res_0402"))
    )
    (comp (ref "R71")
      (value "4K7")
      (footprint "RES0402")
      (fields (field (name "TOLERANCE") "±5%") (field (name "MANUFACTURER") "Stackpole Electronics Inc."))
      (libsource (lib "LimeFPGAboard_schLib") (part "Res_0402"))
    )
    (comp (ref "R72")
      (value "0R")
      (footprint "RES0402")
      (fields (field (name "MANUFACTURER") "Yageo"))
      (libsource (lib "LimeFPGAboard_schLib") (part "Res_0402"))
    )
    (comp (ref "R73")
      (value "4K7")
      (footprint "RES0402")
      (fields (field (name "TOLERANCE") "±5%") (field (name "MANUFACTURER") "Stackpole Electronics Inc."))
      (libsource (lib "LimeFPGAboard_schLib") (part "Res_0402"))
    )
    (comp (ref "R74")
      (value "0R")
      (footprint "RES0402")
      (fields (field (name "MANUFACTURER") "Yageo") (field (name "ASSEMBLY INFO") "NF"))
      (libsource (lib "LimeFPGAboard_schLib") (part "Res_0402"))
    )
    (comp (ref "VT7")
      (value "NDS331N")
      (footprint "SOT23-3")
      (fields (field (name "MANUFACTURER") "Fairchild Semiconductor"))
      (libsource (lib "LimeFPGAboard_schLib") (part "NDS331N"))
    )
  )
  (nets
    (net (code "1") (name "/EXP_AS_SS") (class "Default")
      (node (ref "R74") (pin "1") (pinfunction "1_1") (pintype "passive"))
    )
    (net (code "2") (name "/EXP_AS_SW") (class "Default")
      (node (ref "R64") (pin "2") (pinfunction "2_2") (pintype "passive"))
    )
    (net (code "3") (name "/FAN_CTRL") (class "Default")
      (node (ref "R65") (pin "2") (pinfunction "2_2") (pintype "passive"))
      (node (ref "R67") (pin "1") (pinfunction "1_1") (pintype "passive"))
      (node (ref "VT7") (pin "G") (pinfunction "G_G") (pintype "passive"))
    )
    (net (code "4") (name "/FLASH_AS_MISO") (class "Default")
      (node (ref "IC10") (pin "2") (pinfunction "Q_2") (pintype "passive"))
      (node (ref "IC9") (pin "7") (pinfunction "COM2_7") (pintype "passive"))
    )
    (net (code "5") (name "/FLASH_AS_MOSI") (class "Default")
      (node (ref "IC10") (pin "5") (pinfunction "D_5") (pintype "passive"))
      (node (ref "IC9") (pin "4") (pinfunction "COM1_4") (pintype "passive"))
    )
    (net (code "6") (name "/FLASH_AS_SCLK") (class "Default")
      (node (ref "IC10") (pin "6") (pinfunction "C_6") (pintype "passive"))
      (node (ref "IC9") (pin "9") (pinfunction "COM3_9") (pintype "passive"))
      (node (ref "R69") (pin "1") (pinfunction "1_1") (pintype "passive"))
    )
    (net (code "7") (name "/FLASH_AS_SS") (class "Default")
      (node (ref "IC10") (pin "1") (pinfunction "S_1") (pintype "passive"))
      (node (ref "IC9") (pin "12") (pinfunction "COM4_12") (pintype "passive"))
      (node (ref "R70") (pin "2") (pinfunction "2_2") (pintype "passive"))
    )
    (net (code "8") (name "/FPGA_AS_ASDO") (class "Default")
      (node (ref "IC9") (pin "3") (pinfunction "NO1_3") (pintype "passive"))
    )
    (net (code "9") (name "/FPGA_AS_DATA0") (class "Default")
      (node (ref "R68") (pin "2") (pinfunction "2_2") (pintype "passive"))
    )
    (net (code "10") (name "/FPGA_AS_DCLK") (class "Default")
      (node (ref "IC8") (pin "K2") (pinfunction "DCLK_K2") (pintype "bidirectional"))
      (node (ref "IC9") (pin "10") (pinfunction "NO3_10") (pintype "passive"))
    )
    (net (code "11") (name "/FPGA_AS_NCSO") (class "Default")
      (node (ref "IC9") (pin "13") (pinfunction "NO4_13") (pintype "passive"))
    )
    (net (code "12") (name "/FPGA_CONF_DONE") (class "Default")
      (node (ref "IC8") (pin "M18") (pinfunction "CONF_DONE_M18") (pintype "bidirectional"))
    )
    (net (code "13") (name "/FPGA_GPIO0") (class "Default")
      (node (ref "J12") (pin "1") (pinfunction "1_1") (pintype "passive"))
    )
    (net (code "14") (name "/FPGA_GPIO1") (class "Default")
      (node (ref "J12") (pin "2") (pinfunction "2_2") (pintype "passive"))
    )
    (net (code "15") (name "/FPGA_GPIO2") (class "Default")
      (node (ref "J12") (pin "3") (pinfunction "3_3") (pintype "passive"))
    )
    (net (code "16") (name "/FPGA_GPIO3") (class "Default")
      (node (ref "J12") (pin "4") (pinfunction "4_4") (pintype "passive"))
    )
    (net (code "17") (name "/FPGA_GPIO4") (class "Default")
      (node (ref "J12") (pin "5") (pinfunction "5_5") (pintype "passive"))
    )
    (net (code "18") (name "/FPGA_GPIO5") (class "Default")
      (node (ref "J12") (pin "6") (pinfunction "6_6") (pintype "passive"))
    )
    (net (code "19") (name "/FPGA_GPIO6") (class "Default")
      (node (ref "J12") (pin "7") (pinfunction "7_7") (pintype "passive"))
    )
    (net (code "20") (name "/FPGA_GPIO7") (class "Default")
      (node (ref "J12") (pin "8") (pinfunction "8_8") (pintype "passive"))
    )
    (net (code "21") (name "/FPGA_JTAG_TCK") (class "Default")
      (node (ref "IC8") (pin "L2") (pinfunction "TCK_L2") (pintype "input"))
      (node (ref "J11") (pin "1") (pinfunction "1_1") (pintype "passive"))
      (node (ref "R62") (pin "1") (pinfunction "1_1") (pintype "passive"))
    )
    (net (code "22") (name "/FPGA_JTAG_TDI") (class "Default")
      (node (ref "IC8") (pin "L5") (pinfunction "TDI_L5") (pintype "input"))
      (node (ref "J11") (pin "9") (pinfunction "9_9") (pintype "passive"))
      (node (ref "R58") (pin "1") (pinfunction "1_1") (pintype "passive"))
    )
    (net (code "23") (name "/FPGA_JTAG_TDO") (class "Default")
      (node (ref "IC8") (pin "L4") (pinfunction "TDO_L4") (pintype "output"))
      (node (ref "J11") (pin "3") (pinfunction "3_3") (pintype "passive"))
    )
    (net (code "24") (name "/FPGA_JTAG_TMS") (class "Default")
      (node (ref "IC8") (pin "L1") (pinfunction "TMS_L1") (pintype "input"))
      (node (ref "J11") (pin "5") (pinfunction "5_5") (pintype "passive"))
      (node (ref "R55") (pin "1") (pinfunction "1_1") (pintype "passive"))
    )
    (net (code "25") (name "/FPGA_NCONFIG") (class "Default")
      (node (ref "IC8") (pin "K5") (pinfunction "nCONFIG_K5") (pintype "input"))
    )
    (net (code "26") (name "/FPGA_NSTATUS") (class "Default")
      (node (ref "IC8") (pin "K6") (pinfunction "nSTATUS_K6") (pintype "bidirectional"))
    )
    (net (code "27") (name "/FX3_PCLK") (class "Default")
      (node (ref "IC8") (pin "T21") (pinfunction "CLK6,_DIFFCLK_3p_T21") (pintype "input"))
    )
    (net (code "28") (name "/FX3_SPI_AS_SS") (class "Default")
      (node (ref "R72") (pin "1") (pinfunction "1_1") (pintype "passive"))
    )
    (net (code "29") (name "/FX3_SPI_MISO") (class "Default")
      (node (ref "IC9") (pin "5") (pinfunction "NC2_5") (pintype "passive"))
    )
    (net (code "30") (name "/FX3_SPI_MOSI") (class "Default")
      (node (ref "IC9") (pin "2") (pinfunction "NC1_2") (pintype "passive"))
    )
    (net (code "31") (name "/FX3_SPI_SCLK") (class "Default")
      (node (ref "IC9") (pin "11") (pinfunction "NC3_11") (pintype "passive"))
    )
    (net (code "32") (name "/LM75_OS") (class "Default")
      (node (ref "R65") (pin "1") (pinfunction "1_1") (pintype "passive"))
    )
    (net (code "33") (name "/LMK_CLK") (class "Default")
      (node (ref "IC8") (pin "B12") (pinfunction "CLK9,_DIFFCLK_5p_B12") (pintype "input"))
    )
    (net (code "34") (name "/LMS_MCLK1") (class "Default")
      (node (ref "IC8") (pin "G21") (pinfunction "CLK4,_DIFFCLK_2p_G21") (pintype "input"))
    )
    (net (code "35") (name "/LMS_MCLK2") (class "Default")
      (node (ref "IC8") (pin "B11") (pinfunction "CLK11,_DIFFCLK_4p_B11") (pintype "input"))
    )
    (net (code "36") (name "/MSEL0") (class "Default")
      (node (ref "IC8") (pin "M17") (pinfunction "MSEL0_M17") (pintype "input"))
      (node (ref "R51") (pin "1") (pinfunction "1_1") (pintype "passive"))
      (node (ref "R52") (pin "2") (pinfunction "2_2") (pintype "passive"))
    )
    (net (code "37") (name "/MSEL1") (class "Default")
      (node (ref "IC8") (pin "L18") (pinfunction "MSEL1_L18") (pintype "input"))
      (node (ref "R53") (pin "1") (pinfunction "1_1") (pintype "passive"))
      (node (ref "R54") (pin "2") (pinfunction "2_2") (pintype "passive"))
    )
    (net (code "38") (name "/MSEL2") (class "Default")
      (node (ref "IC8") (pin "L17") (pinfunction "MSEL2_L17") (pintype "input"))
      (node (ref "R56") (pin "1") (pinfunction "1_1") (pintype "passive"))
      (node (ref "R57") (pin "2") (pinfunction "2_2") (pintype "passive"))
    )
    (net (code "39") (name "/MSEL3") (class "Default")
      (node (ref "IC8") (pin "K20") (pinfunction "MSEL3_K20") (pintype "input"))
      (node (ref "R59") (pin "1") (pinfunction "1_1") (pintype "passive"))
      (node (ref "R60") (pin "2") (pinfunction "2_2") (pintype "passive"))
    )
    (net (code "40") (name "/SI_CLK0") (class "Default")
      (node (ref "IC8") (pin "T2") (pinfunction "CLK2,_DIFFCLK_1p_T2") (pintype "input"))
    )
    (net (code "41") (name "/SI_CLK1") (class "Default")
      (node (ref "IC8") (pin "AA12") (pinfunction "CLK13,_DIFFCLK_7p_AA12") (pintype "input"))
    )
    (net (code "42") (name "/SI_CLK2") (class "Default")
      (node (ref "IC8") (pin "AB12") (pinfunction "CLK12,_DIFFCLK_7n_AB12") (pintype "input"))
    )
    (net (code "43") (name "/SI_CLK3") (class "Default")
      (node (ref "IC8") (pin "T22") (pinfunction "CLK7,_DIFFCLK_3n_T22") (pintype "input"))
    )
    (net (code "44") (name "/SI_CLK5") (class "Default")
      (node (ref "IC8") (pin "G1") (pinfunction "CLK1,_DIFFCLK_0n_G1") (pintype "input"))
    )
    (net (code "45") (name "/SI_CLK6") (class "Default")
      (node (ref "IC8") (pin "AA11") (pinfunction "CLK15,_DIFFCLK_6p_AA11") (pintype "input"))
    )
    (net (code "46") (name "/SI_CLK7") (class "Default")
      (node (ref "IC8") (pin "AB11") (pinfunction "CLK14,_DIFFCLK_6n_AB11") (pintype "input"))
    )
    (net (code "47") (name "GND") (class "Default")
      (node (ref "C115") (pin "1") (pinfunction "1_1") (pintype "passive"))
      (node (ref "C116") (pin "1") (pinfunction "1_1") (pintype "passive"))
      (node (ref "C117") (pin "1") (pinfunction "1_1") (pintype "passive"))
      (node (ref "C118") (pin "2") (pinfunction "2_2") (pintype "passive"))
      (node (ref "C119") (pin "2") (pinfunction "2_2") (pintype "passive"))
      (node (ref "C120") (pin "1") (pinfunction "1_1") (pintype "passive"))
      (node (ref "C121") (pin "1") (pinfunction "1_1") (pintype "passive"))
      (node (ref "C122") (pin "1") (pinfunction "1_1") (pintype "passive"))
      (node (ref "C123") (pin "2") (pinfunction "2_2") (pintype "passive"))
      (node (ref "C124") (pin "2") (pinfunction "2_2") (pintype "passive"))
      (node (ref "C125") (pin "2") (pinfunction "2_2") (pintype "passive"))
      (node (ref "C126") (pin "1") (pinfunction "1_1") (pintype "passive"))
      (node (ref "C127") (pin "1") (pinfunction "1_1") (pintype "passive"))
      (node (ref "C128") (pin "1") (pinfunction "1_1") (pintype "passive"))
      (node (ref "C129") (pin "1") (pinfunction "1_1") (pintype "passive"))
      (node (ref "C130") (pin "1") (pinfunction "1_1") (pintype "passive"))
      (node (ref "C131") (pin "2") (pinfunction "2_2") (pintype "passive"))
      (node (ref "C132") (pin "1") (pinfunction "1_1") (pintype "passive"))
      (node (ref "C133") (pin "1") (pinfunction "1_1") (pintype "passive"))
      (node (ref "C134") (pin "1") (pinfunction "1_1") (pintype "passive"))
      (node (ref "C135") (pin "1") (pinfunction "1_1") (pintype "passive"))
      (node (ref "C136") (pin "2") (pinfunction "2_2") (pintype "passive"))
      (node (ref "C137") (pin "1") (pinfunction "1_1") (pintype "passive"))
      (node (ref "C138") (pin "1") (pinfunction "1_1") (pintype "passive"))
      (node (ref "C139") (pin "1") (pinfunction "1_1") (pintype "passive"))
      (node (ref "C140") (pin "1") (pinfunction "1_1") (pintype "passive"))
      (node (ref "C141") (pin "2") (pinfunction "2_2") (pintype "passive"))
      (node (ref "C142") (pin "1") (pinfunction "1_1") (pintype "passive"))
      (node (ref "C143") (pin "1") (pinfunction "1_1") (pintype "passive"))
      (node (ref "C144") (pin "1") (pinfunction "1_1") (pintype "passive"))
      (node (ref "C145") (pin "1") (pinfunction "1_1") (pintype "passive"))
      (node (ref "C146") (pin "2") (pinfunction "2_2") (pintype "passive"))
      (node (ref "C147") (pin "2") (pinfunction "2_2") (pintype "passive"))
      (node (ref "C148") (pin "2") (pinfunction "2_2") (pintype "passive"))
      (node (ref "C149") (pin "2") (pinfunction "2_2") (pintype "passive"))
      (node (ref "C150") (pin "2") (pinfunction "2_2") (pintype "passive"))
      (node (ref "C151") (pin "2") (pinfunction "2_2") (pintype "passive"))
      (node (ref "C152") (pin "2") (pinfunction "2_2") (pintype "passive"))
      (node (ref "C153") (pin "2") (pinfunction "2_2") (pintype "passive"))
      (node (ref "C154") (pin "2") (pinfunction "2_2") (pintype "passive"))
      (node (ref "C155") (pin "2") (pinfunction "2_2") (pintype "passive"))
      (node (ref "C156") (pin "2") (pinfunction "2_2") (pintype "passive"))
      (node (ref "C157") (pin "2") (pinfunction "2_2") (pintype "passive"))
      (node (ref "C158") (pin "2") (pinfunction "2_2") (pintype "passive"))
      (node (ref "C159") (pin "2") (pinfunction "2_2") (pintype "passive"))
      (node (ref "C160") (pin "2") (pinfunction "2_2") (pintype "passive"))
      (node (ref "C161") (pin "2") (pinfunction "2_2") (pintype "passive"))
      (node (ref "C162") (pin "2") (pinfunction "2_2") (pintype "passive"))
      (node (ref "C163") (pin "2") (pinfunction "2_2") (pintype "passive"))
      (node (ref "C164") (pin "2") (pinfunction "2_2") (pintype "passive"))
      (node (ref "C165") (pin "2") (pinfunction "2_2") (pintype "passive"))
      (node (ref "C166") (pin "2") (pinfunction "2_2") (pintype "passive"))
      (node (ref "C167") (pin "2") (pinfunction "2_2") (pintype "passive"))
      (node (ref "C168") (pin "2") (pinfunction "2_2") (pintype "passive"))
      (node (ref "C169") (pin "2") (pinfunction "2_2") (pintype "passive"))
      (node (ref "C170") (pin "2") (pinfunction "2_2") (pintype "passive"))
      (node (ref "C171") (pin "2") (pinfunction "2_2") (pintype "passive"))
      (node (ref "C172") (pin "2") (pinfunction "2_2") (pintype "passive"))
      (node (ref "C173") (pin "2") (pinfunction "2_2") (pintype "passive"))
      (node (ref "C174") (pin "2") (pinfunction "2_2") (pintype "passive"))
      (node (ref "C175") (pin "2") (pinfunction "2_2") (pintype "passive"))
      (node (ref "C176") (pin "2") (pinfunction "2_2") (pintype "passive"))
      (node (ref "C177") (pin "2") (pinfunction "2_2") (pintype "passive"))
      (node (ref "C178") (pin "2") (pinfunction "2_2") (pintype "passive"))
      (node (ref "C179") (pin "2") (pinfunction "2_2") (pintype "passive"))
      (node (ref "C180") (pin "2") (pinfunction "2_2") (pintype "passive"))
      (node (ref "C181") (pin "2") (pinfunction "2_2") (pintype "passive"))
      (node (ref "C182") (pin "2") (pinfunction "2_2") (pintype "passive"))
      (node (ref "C183") (pin "2") (pinfunction "2_2") (pintype "passive"))
      (node (ref "C184") (pin "2") (pinfunction "2_2") (pintype "passive"))
      (node (ref "C185") (pin "2") (pinfunction "2_2") (pintype "passive"))
      (node (ref "C186") (pin "2") (pinfunction "2_2") (pintype "passive"))
      (node (ref "C187") (pin "2") (pinfunction "2_2") (pintype "passive"))
      (node (ref "C188") (pin "2") (pinfunction "2_2") (pintype "passive"))
      (node (ref "C189") (pin "2") (pinfunction "2_2") (pintype "passive"))
      (node (ref "C190") (pin "2") (pinfunction "2_2") (pintype "passive"))
      (node (ref "C191") (pin "2") (pinfunction "2_2") (pintype "passive"))
      (node (ref "C192") (pin "2") (pinfunction "2_2") (pintype "passive"))
      (node (ref "C193") (pin "2") (pinfunction "2_2") (pintype "passive"))
      (node (ref "C194") (pin "2") (pinfunction "2_2") (pintype "passive"))
      (node (ref "C195") (pin "2") (pinfunction "2_2") (pintype "passive"))
      (node (ref "C196") (pin "2") (pinfunction "2_2") (pintype "passive"))
      (node (ref "C197") (pin "2") (pinfunction "2_2") (pintype "passive"))
      (node (ref "C198") (pin "2") (pinfunction "2_2") (pintype "passive"))
      (node (ref "C199") (pin "2") (pinfunction "2_2") (pintype "passive"))
      (node (ref "C200") (pin "2") (pinfunction "2_2") (pintype "passive"))
      (node (ref "C201") (pin "2") (pinfunction "2_2") (pintype "passive"))
      (node (ref "C202") (pin "2") (pinfunction "2_2") (pintype "passive"))
      (node (ref "C203") (pin "2") (pinfunction "2_2") (pintype "passive"))
      (node (ref "C204") (pin "2") (pinfunction "2_2") (pintype "passive"))
      (node (ref "C205") (pin "2") (pinfunction "2_2") (pintype "passive"))
      (node (ref "C206") (pin "2") (pinfunction "2_2") (pintype "passive"))
      (node (ref "C207") (pin "2") (pinfunction "2_2") (pintype "passive"))
      (node (ref "C208") (pin "2") (pinfunction "2_2") (pintype "passive"))
      (node (ref "C209") (pin "2") (pinfunction "2_2") (pintype "passive"))
      (node (ref "C210") (pin "2") (pinfunction "2_2") (pintype "passive"))
      (node (ref "C211") (pin "2") (pinfunction "2_2") (pintype "passive"))
      (node (ref "C212") (pin "2") (pinfunction "2_2") (pintype "passive"))
      (node (ref "C213") (pin "2") (pinfunction "2_2") (pintype "passive"))
      (node (ref "C214") (pin "2") (pinfunction "2_2") (pintype "passive"))
      (node (ref "C215") (pin "2") (pinfunction "2_2") (pintype "passive"))
      (node (ref "C216") (pin "2") (pinfunction "2_2") (pintype "passive"))
      (node (ref "C217") (pin "2") (pinfunction "2_2") (pintype "passive"))
      (node (ref "C218") (pin "2") (pinfunction "2_2") (pintype "passive"))
      (node (ref "C219") (pin "2") (pinfunction "2_2") (pintype "passive"))
      (node (ref "C220") (pin "2") (pinfunction "2_2") (pintype "passive"))
      (node (ref "IC10") (pin "4") (pinfunction "GND_4") (pintype "passive"))
      (node (ref "IC8") (pin "A1") (pinfunction "GND_A1") (pintype "power_in"))
      (node (ref "IC8") (pin "A11") (pinfunction "CLK10,_DIFFCLK_4n_A11") (pintype "input"))
      (node (ref "IC8") (pin "A12") (pinfunction "CLK8,_DIFFCLK_5n_A12") (pintype "input"))
      (node (ref "IC8") (pin "A22") (pinfunction "GND_A22") (pintype "power_in"))
      (node (ref "IC8") (pin "AA2") (pinfunction "GND_AA2") (pintype "power_in"))
      (node (ref "IC8") (pin "AA22") (pinfunction "GND_AA22") (pintype "power_in"))
      (node (ref "IC8") (pin "AB1") (pinfunction "GND_AB1") (pintype "power_in"))
      (node (ref "IC8") (pin "AB22") (pinfunction "GND_AB22") (pintype "power_in"))
      (node (ref "IC8") (pin "AB6") (pinfunction "GND_AB6") (pintype "power_in"))
      (node (ref "IC8") (pin "C11") (pinfunction "GND_C11") (pintype "power_in"))
      (node (ref "IC8") (pin "C12") (pinfunction "GND_C12") (pintype "power_in"))
      (node (ref "IC8") (pin "C14") (pinfunction "GND_C14") (pintype "power_in"))
      (node (ref "IC8") (pin "C16") (pinfunction "GND_C16") (pintype "power_in"))
      (node (ref "IC8") (pin "C18") (pinfunction "GND_C18") (pintype "power_in"))
      (node (ref "IC8") (pin "C5") (pinfunction "GND_C5") (pintype "power_in"))
      (node (ref "IC8") (pin "C9") (pinfunction "GND_C9") (pintype "power_in"))
      (node (ref "IC8") (pin "D3") (pinfunction "GND_D3") (pintype "power_in"))
      (node (ref "IC8") (pin "D8") (pinfunction "GND_D8") (pintype "power_in"))
      (node (ref "IC8") (pin "E18") (pinfunction "GNDA2_E18") (pintype "power_in"))
      (node (ref "IC8") (pin "E20") (pinfunction "GND_E20") (pintype "power_in"))
      (node (ref "IC8") (pin "F12") (pinfunction "GND_F12") (pintype "power_in"))
      (node (ref "IC8") (pin "F3") (pinfunction "GND_F3") (pintype "power_in"))
      (node (ref "IC8") (pin "F5") (pinfunction "GNDA3_F5") (pintype "power_in"))
      (node (ref "IC8") (pin "G2") (pinfunction "GND_G2") (pintype "power_in"))
      (node (ref "IC8") (pin "G20") (pinfunction "GND_G20") (pintype "power_in"))
      (node (ref "IC8") (pin "G22") (pinfunction "CLK5,_DIFFCLK_2n_G22") (pintype "input"))
      (node (ref "IC8") (pin "H12") (pinfunction "GND_H12") (pintype "power_in"))
      (node (ref "IC8") (pin "H13") (pinfunction "GND_H13") (pintype "power_in"))
      (node (ref "IC8") (pin "H3") (pinfunction "GND_H3") (pintype "power_in"))
      (node (ref "IC8") (pin "J15") (pinfunction "GND_J15") (pintype "power_in"))
      (node (ref "IC8") (pin "J19") (pinfunction "GND_J19") (pintype "power_in"))
      (node (ref "IC8") (pin "J9") (pinfunction "GND_J9") (pintype "power_in"))
      (node (ref "IC8") (pin "K10") (pinfunction "GND_K10") (pintype "power_in"))
      (node (ref "IC8") (pin "K11") (pinfunction "GND_K11") (pintype "power_in"))
      (node (ref "IC8") (pin "K12") (pinfunction "GND_K12") (pintype "power_in"))
      (node (ref "IC8") (pin "K13") (pinfunction "GND_K13") (pintype "power_in"))
      (node (ref "IC8") (pin "K16") (pinfunction "GND_K16") (pintype "power_in"))
      (node (ref "IC8") (pin "K3") (pinfunction "GND_K3") (pintype "power_in"))
      (node (ref "IC8") (pin "L10") (pinfunction "GND_L10") (pintype "power_in"))
      (node (ref "IC8") (pin "L11") (pinfunction "GND_L11") (pintype "power_in"))
      (node (ref "IC8") (pin "L12") (pinfunction "GND_L12") (pintype "power_in"))
      (node (ref "IC8") (pin "L13") (pinfunction "GND_L13") (pintype "power_in"))
      (node (ref "IC8") (pin "L15") (pinfunction "GND_L15") (pintype "power_in"))
      (node (ref "IC8") (pin "L20") (pinfunction "GND_L20") (pintype "power_in"))
      (node (ref "IC8") (pin "L3") (pinfunction "nCE_L3") (pintype "input"))
      (node (ref "IC8") (pin "M10") (pinfunction "GND_M10") (pintype "power_in"))
      (node (ref "IC8") (pin "M11") (pinfunction "GND_M11") (pintype "power_in"))
      (node (ref "IC8") (pin "M12") (pinfunction "GND_M12") (pintype "power_in"))
      (node (ref "IC8") (pin "M13") (pinfunction "GND_M13") (pintype "power_in"))
      (node (ref "IC8") (pin "N10") (pinfunction "GND_N10") (pintype "power_in"))
      (node (ref "IC8") (pin "N11") (pinfunction "GND_N11") (pintype "power_in"))
      (node (ref "IC8") (pin "N12") (pinfunction "GND_N12") (pintype "power_in"))
      (node (ref "IC8") (pin "N13") (pinfunction "GND_N13") (pintype "power_in"))
      (node (ref "IC8") (pin "N15") (pinfunction "GND_N15") (pintype "power_in"))
      (node (ref "IC8") (pin "N3") (pinfunction "GND_N3") (pintype "power_in"))
      (node (ref "IC8") (pin "P19") (pinfunction "GND_P19") (pintype "power_in"))
      (node (ref "IC8") (pin "P8") (pinfunction "GND_P8") (pintype "power_in"))
      (node (ref "IC8") (pin "R11") (pinfunction "GND_R11") (pintype "power_in"))
      (node (ref "IC8") (pin "R13") (pinfunction "GND_R13") (pintype "power_in"))
      (node (ref "IC8") (pin "R3") (pinfunction "GND_R3") (pintype "power_in"))
      (node (ref "IC8") (pin "R9") (pinfunction "GND_R9") (pintype "power_in"))
      (node (ref "IC8") (pin "T1") (pinfunction "CLK3,_DIFFCLK_1n_T1") (pintype "input"))
      (node (ref "IC8") (pin "T20") (pinfunction "GND_T20") (pintype "power_in"))
      (node (ref "IC8") (pin "U3") (pinfunction "GND_U3") (pintype "power_in"))
      (node (ref "IC8") (pin "U5") (pinfunction "GNDA1_U5") (pintype "power_in"))
      (node (ref "IC8") (pin "V18") (pinfunction "GNDA4_V18") (pintype "power_in"))
      (node (ref "IC8") (pin "V20") (pinfunction "GND_V20") (pintype "power_in"))
      (node (ref "IC8") (pin "W3") (pinfunction "GND_W3") (pintype "power_in"))
      (node (ref "IC8") (pin "Y11") (pinfunction "GND_Y11") (pintype "power_in"))
      (node (ref "IC8") (pin "Y12") (pinfunction "GND_Y12") (pintype "power_in"))
      (node (ref "IC8") (pin "Y15") (pinfunction "GND_Y15") (pintype "power_in"))
      (node (ref "IC8") (pin "Y16") (pinfunction "GND_Y16") (pintype "power_in"))
      (node (ref "IC8") (pin "Y18") (pinfunction "GND_Y18") (pintype "power_in"))
      (node (ref "IC8") (pin "Y20") (pinfunction "GND_Y20") (pintype "power_in"))
      (node (ref "IC8") (pin "Y5") (pinfunction "GND_Y5") (pintype "power_in"))
      (node (ref "IC8") (pin "Y9") (pinfunction "GND_Y9") (pintype "power_in"))
      (node (ref "IC9") (pin "15") (pinfunction "~{EN}_15") (pintype "passive"))
      (node (ref "IC9") (pin "8") (pinfunction "GND_8") (pintype "passive"))
      (node (ref "J11") (pin "10") (pinfunction "10_10") (pintype "passive"))
      (node (ref "J11") (pin "2") (pinfunction "2_2") (pintype "passive"))
      (node (ref "J12") (pin "9") (pinfunction "9_9") (pintype "passive"))
      (node (ref "R51") (pin "2") (pinfunction "2_2") (pintype "passive"))
      (node (ref "R53") (pin "2") (pinfunction "2_2") (pintype "passive"))
      (node (ref "R56") (pin "2") (pinfunction "2_2") (pintype "passive"))
      (node (ref "R59") (pin "2") (pinfunction "2_2") (pintype "passive"))
      (node (ref "R62") (pin "2") (pinfunction "2_2") (pintype "passive"))
      (node (ref "R67") (pin "2") (pinfunction "2_2") (pintype "passive"))
      (node (ref "R69") (pin "2") (pinfunction "2_2") (pintype "passive"))
      (node (ref "VT7") (pin "S") (pinfunction "S_S") (pintype "passive"))
    )
    (net (code "48") (name "Net-(IC9-IN)") (class "Default")
      (node (ref "IC9") (pin "1") (pinfunction "IN_1") (pintype "passive"))
      (node (ref "R64") (pin "1") (pinfunction "1_1") (pintype "passive"))
      (node (ref "R66") (pin "2") (pinfunction "2_2") (pintype "passive"))
    )
    (net (code "49") (name "Net-(IC9-NC4)") (class "Default")
      (node (ref "IC9") (pin "14") (pinfunction "NC4_14") (pintype "passive"))
      (node (ref "R72") (pin "2") (pinfunction "2_2") (pintype "passive"))
      (node (ref "R74") (pin "2") (pinfunction "2_2") (pintype "passive"))
    )
    (net (code "50") (name "Net-(IC9-NO2)") (class "Default")
      (node (ref "IC9") (pin "6") (pinfunction "NO2_6") (pintype "passive"))
      (node (ref "R68") (pin "1") (pinfunction "1_1") (pintype "passive"))
    )
    (net (code "51") (name "Net-(IC10-HOLD)") (class "Default")
      (node (ref "IC10") (pin "7") (pinfunction "HOLD_7") (pintype "passive"))
      (node (ref "R71") (pin "2") (pinfunction "2_2") (pintype "passive"))
    )
    (net (code "52") (name "Net-(IC10-W)") (class "Default")
      (node (ref "IC10") (pin "3") (pinfunction "W_3") (pintype "passive"))
      (node (ref "R73") (pin "2") (pinfunction "2_2") (pintype "passive"))
    )
    (net (code "53") (name "Net-(J12-Pad10)") (class "Default")
      (node (ref "J12") (pin "10") (pinfunction "10_10") (pintype "passive"))
      (node (ref "R61") (pin "2") (pinfunction "2_2") (pintype "passive"))
      (node (ref "R63") (pin "2") (pinfunction "2_2") (pintype "passive"))
    )
    (net (code "54") (name "Net-(J13-Pad1)") (class "Default")
      (node (ref "J13") (pin "1") (pinfunction "1_1") (pintype "passive"))
      (node (ref "J14") (pin "1") (pinfunction "1_1") (pintype "passive"))
      (node (ref "VT7") (pin "D") (pinfunction "D_D") (pintype "passive"))
    )
    (net (code "55") (name "VCC1P2") (class "Default")
      (node (ref "C115") (pin "2") (pinfunction "2_2") (pintype "passive"))
      (node (ref "C116") (pin "2") (pinfunction "2_2") (pintype "passive"))
      (node (ref "C117") (pin "2") (pinfunction "2_2") (pintype "passive"))
      (node (ref "C118") (pin "1") (pinfunction "1_1") (pintype "passive"))
      (node (ref "C119") (pin "1") (pinfunction "1_1") (pintype "passive"))
      (node (ref "C189") (pin "1") (pinfunction "1_1") (pintype "passive"))
      (node (ref "C190") (pin "1") (pinfunction "1_1") (pintype "passive"))
      (node (ref "C191") (pin "1") (pinfunction "1_1") (pintype "passive"))
      (node (ref "C192") (pin "1") (pinfunction "1_1") (pintype "passive"))
      (node (ref "C193") (pin "1") (pinfunction "1_1") (pintype "passive"))
      (node (ref "C194") (pin "1") (pinfunction "1_1") (pintype "passive"))
      (node (ref "C195") (pin "1") (pinfunction "1_1") (pintype "passive"))
      (node (ref "C196") (pin "1") (pinfunction "1_1") (pintype "passive"))
      (node (ref "C197") (pin "1") (pinfunction "1_1") (pintype "passive"))
      (node (ref "C198") (pin "1") (pinfunction "1_1") (pintype "passive"))
      (node (ref "C199") (pin "1") (pinfunction "1_1") (pintype "passive"))
      (node (ref "C200") (pin "1") (pinfunction "1_1") (pintype "passive"))
      (node (ref "C201") (pin "1") (pinfunction "1_1") (pintype "passive"))
      (node (ref "C202") (pin "1") (pinfunction "1_1") (pintype "passive"))
      (node (ref "C207") (pin "1") (pinfunction "1_1") (pintype "passive"))
      (node (ref "C208") (pin "1") (pinfunction "1_1") (pintype "passive"))
      (node (ref "C209") (pin "1") (pinfunction "1_1") (pintype "passive"))
      (node (ref "C210") (pin "1") (pinfunction "1_1") (pintype "passive"))
      (node (ref "C211") (pin "1") (pinfunction "1_1") (pintype "passive"))
      (node (ref "C212") (pin "1") (pinfunction "1_1") (pintype "passive"))
      (node (ref "C213") (pin "1") (pinfunction "1_1") (pintype "passive"))
      (node (ref "C214") (pin "1") (pinfunction "1_1") (pintype "passive"))
      (node (ref "C215") (pin "1") (pinfunction "1_1") (pintype "passive"))
      (node (ref "C216") (pin "1") (pinfunction "1_1") (pintype "passive"))
      (node (ref "C217") (pin "1") (pinfunction "1_1") (pintype "passive"))
      (node (ref "C218") (pin "1") (pinfunction "1_1") (pintype "passive"))
      (node (ref "C219") (pin "1") (pinfunction "1_1") (pintype "passive"))
      (node (ref "C220") (pin "1") (pinfunction "1_1") (pintype "passive"))
      (node (ref "FR36") (pin "1") (pinfunction "1_1") (pintype "passive"))
      (node (ref "IC8") (pin "G12") (pinfunction "VCCINT_G12") (pintype "power_in"))
      (node (ref "IC8") (pin "H9") (pinfunction "VCCINT_H9") (pintype "power_in"))
      (node (ref "IC8") (pin "J10") (pinfunction "VCCINT_J10") (pintype "power_in"))
      (node (ref "IC8") (pin "J11") (pinfunction "VCCINT_J11") (pintype "power_in"))
      (node (ref "IC8") (pin "J12") (pinfunction "VCCINT_J12") (pintype "power_in"))
      (node (ref "IC8") (pin "J13") (pinfunction "VCCINT_J13") (pintype "power_in"))
      (node (ref "IC8") (pin "J14") (pinfunction "VCCINT_J14") (pintype "power_in"))
      (node (ref "IC8") (pin "J16") (pinfunction "VCCINT_J16") (pintype "power_in"))
      (node (ref "IC8") (pin "K14") (pinfunction "VCCINT_K14") (pintype "power_in"))
      (node (ref "IC8") (pin "K15") (pinfunction "VCCINT_K15") (pintype "power_in"))
      (node (ref "IC8") (pin "K9") (pinfunction "VCCINT_K9") (pintype "power_in"))
      (node (ref "IC8") (pin "L14") (pinfunction "VCCINT_L14") (pintype "power_in"))
      (node (ref "IC8") (pin "L16") (pinfunction "VCCINT_L16") (pintype "power_in"))
      (node (ref "IC8") (pin "L9") (pinfunction "VCCINT_L9") (pintype "power_in"))
      (node (ref "IC8") (pin "M14") (pinfunction "VCCINT_M14") (pintype "power_in"))
      (node (ref "IC8") (pin "M15") (pinfunction "VCCINT_M15") (pintype "power_in"))
      (node (ref "IC8") (pin "M9") (pinfunction "VCCINT_M9") (pintype "power_in"))
      (node (ref "IC8") (pin "N14") (pinfunction "VCCINT_N14") (pintype "power_in"))
      (node (ref "IC8") (pin "N9") (pinfunction "VCCINT_N9") (pintype "power_in"))
      (node (ref "IC8") (pin "P10") (pinfunction "VCCINT_P10") (pintype "power_in"))
      (node (ref "IC8") (pin "P11") (pinfunction "VCCINT_P11") (pintype "power_in"))
      (node (ref "IC8") (pin "P12") (pinfunction "VCCINT_P12") (pintype "power_in"))
      (node (ref "IC8") (pin "P13") (pinfunction "VCCINT_P13") (pintype "power_in"))
      (node (ref "IC8") (pin "P14") (pinfunction "VCCINT_P14") (pintype "power_in"))
      (node (ref "IC8") (pin "P9") (pinfunction "VCCINT_P9") (pintype "power_in"))
      (node (ref "IC8") (pin "R10") (pinfunction "VCCINT_R10") (pintype "power_in"))
      (node (ref "IC8") (pin "R12") (pinfunction "VCCINT_R12") (pintype "power_in"))
      (node (ref "IC8") (pin "R8") (pinfunction "VCCINT_R8") (pintype "power_in"))
    )
    (net (code "56") (name "VCC1P2D_FPGA") (class "Default")
      (node (ref "C120") (pin "2") (pinfunction "2_2") (pintype "passive"))
      (node (ref "C121") (pin "2") (pinfunction "2_2") (pintype "passive"))
      (node (ref "C122") (pin "2") (pinfunction "2_2") (pintype "passive"))
      (node (ref "C123") (pin "1") (pinfunction "1_1") (pintype "passive"))
      (node (ref "C124") (pin "1") (pinfunction "1_1") (pintype "passive"))
      (node (ref "C203") (pin "1") (pinfunction "1_1") (pintype "passive"))
      (node (ref "C204") (pin "1") (pinfunction "1_1") (pintype "passive"))
      (node (ref "C205") (pin "1") (pinfunction "1_1") (pintype "passive"))
      (node (ref "C206") (pin "1") (pinfunction "1_1") (pintype "passive"))
      (node (ref "FR36") (pin "2") (pinfunction "2_2") (pintype "passive"))
      (node (ref "IC8") (pin "E17") (pinfunction "VCCD_PLL2_E17") (pintype "power_in"))
      (node (ref "IC8") (pin "F6") (pinfunction "VCCD_PLL3_F6") (pintype "power_in"))
      (node (ref "IC8") (pin "U6") (pinfunction "VCCD_PLL1_U6") (pintype "power_in"))
      (node (ref "IC8") (pin "V17") (pinfunction "VCCD_PLL4_V17") (pintype "power_in"))
    )
    (net (code "57") (name "VCC1P8") (class "Default")
      (node (ref "C126") (pin "2") (pinfunction "2_2") (pintype "passive"))
      (node (ref "C127") (pin "2") (pinfunction "2_2") (pintype "passive"))
      (node (ref "C128") (pin "2") (pinfunction "2_2") (pintype "passive"))
      (node (ref "C129") (pin "2") (pinfunction "2_2") (pintype "passive"))
      (node (ref "C130") (pin "2") (pinfunction "2_2") (pintype "passive"))
      (node (ref "C131") (pin "1") (pinfunction "1_1") (pintype "passive"))
      (node (ref "C171") (pin "1") (pinfunction "1_1") (pintype "passive"))
      (node (ref "C172") (pin "1") (pinfunction "1_1") (pintype "passive"))
      (node (ref "C173") (pin "1") (pinfunction "1_1") (pintype "passive"))
      (node (ref "C174") (pin "1") (pinfunction "1_1") (pintype "passive"))
      (node (ref "C175") (pin "1") (pinfunction "1_1") (pintype "passive"))
      (node (ref "C176") (pin "1") (pinfunction "1_1") (pintype "passive"))
      (node (ref "C177") (pin "1") (pinfunction "1_1") (pintype "passive"))
      (node (ref "C178") (pin "1") (pinfunction "1_1") (pintype "passive"))
      (node (ref "C179") (pin "1") (pinfunction "1_1") (pintype "passive"))
      (node (ref "C180") (pin "1") (pinfunction "1_1") (pintype "passive"))
      (node (ref "C181") (pin "1") (pinfunction "1_1") (pintype "passive"))
      (node (ref "C182") (pin "1") (pinfunction "1_1") (pintype "passive"))
      (node (ref "C183") (pin "1") (pinfunction "1_1") (pintype "passive"))
      (node (ref "C184") (pin "1") (pinfunction "1_1") (pintype "passive"))
      (node (ref "C185") (pin "1") (pinfunction "1_1") (pintype "passive"))
      (node (ref "C186") (pin "1") (pinfunction "1_1") (pintype "passive"))
      (node (ref "C187") (pin "1") (pinfunction "1_1") (pintype "passive"))
      (node (ref "C188") (pin "1") (pinfunction "1_1") (pintype "passive"))
      (node (ref "IC8") (pin "AA6") (pinfunction "VCCIO3_AA6") (pintype "power_in"))
      (node (ref "IC8") (pin "AB2") (pinfunction "VCCIO3_AB2") (pintype "power_in"))
      (node (ref "IC8") (pin "AB21") (pinfunction "VCCIO4_AB21") (pintype "power_in"))
      (node (ref "IC8") (pin "N4") (pinfunction "VCCIO2_N4") (pintype "power_in"))
      (node (ref "IC8") (pin "P18") (pinfunction "VCCIO5_P18") (pintype "power_in"))
      (node (ref "IC8") (pin "R4") (pinfunction "VCCIO2_R4") (pintype "power_in"))
      (node (ref "IC8") (pin "T19") (pinfunction "VCCIO5_T19") (pintype "power_in"))
      (node (ref "IC8") (pin "U4") (pinfunction "VCCIO2_U4") (pintype "power_in"))
      (node (ref "IC8") (pin "V19") (pinfunction "VCCIO5_V19") (pintype "power_in"))
      (node (ref "IC8") (pin "W11") (pinfunction "VCCIO3_W11") (pintype "power_in"))
      (node (ref "IC8") (pin "W12") (pinfunction "VCCIO4_W12") (pintype "power_in"))
      (node (ref "IC8") (pin "W16") (pinfunction "VCCIO4_W16") (pintype "power_in"))
      (node (ref "IC8") (pin "W18") (pinfunction "VCCIO4_W18") (pintype "power_in"))
      (node (ref "IC8") (pin "W4") (pinfunction "VCCIO2_W4") (pintype "power_in"))
      (node (ref "IC8") (pin "W5") (pinfunction "VCCIO3_W5") (pintype "power_in"))
      (node (ref "IC8") (pin "W9") (pinfunction "VCCIO3_W9") (pintype "power_in"))
      (node (ref "IC8") (pin "Y14") (pinfunction "VCCIO4_Y14") (pintype "power_in"))
      (node (ref "IC8") (pin "Y19") (pinfunction "VCCIO5_Y19") (pintype "power_in"))
    )
    (net (code "58") (name "VCC2P5") (class "Default")
      (node (ref "FR37") (pin "1") (pinfunction "1_1") (pintype "passive"))
    )
    (net (code "59") (name "VCC2P5A_FPGA") (class "Default")
      (node (ref "C132") (pin "2") (pinfunction "2_2") (pintype "passive"))
      (node (ref "C133") (pin "2") (pinfunction "2_2") (pintype "passive"))
      (node (ref "C134") (pin "2") (pinfunction "2_2") (pintype "passive"))
      (node (ref "C135") (pin "2") (pinfunction "2_2") (pintype "passive"))
      (node (ref "C136") (pin "1") (pinfunction "1_1") (pintype "passive"))
      (node (ref "C149") (pin "1") (pinfunction "1_1") (pintype "passive"))
      (node (ref "C150") (pin "1") (pinfunction "1_1") (pintype "passive"))
      (node (ref "C151") (pin "1") (pinfunction "1_1") (pintype "passive"))
      (node (ref "C152") (pin "1") (pinfunction "1_1") (pintype "passive"))
      (node (ref "FR37") (pin "2") (pinfunction "2_2") (pintype "passive"))
      (node (ref "IC8") (pin "F18") (pinfunction "VCCA2_F18") (pintype "power_in"))
      (node (ref "IC8") (pin "G6") (pinfunction "VCCA3_G6") (pintype "power_in"))
      (node (ref "IC8") (pin "T6") (pinfunction "VCCA1_T6") (pintype "power_in"))
      (node (ref "IC8") (pin "U18") (pinfunction "VCCA4_U18") (pintype "power_in"))
      (node (ref "J11") (pin "4") (pinfunction "4_4") (pintype "passive"))
      (node (ref "R52") (pin "1") (pinfunction "1_1") (pintype "passive"))
      (node (ref "R54") (pin "1") (pinfunction "1_1") (pintype "passive"))
      (node (ref "R55") (pin "2") (pinfunction "2_2") (pintype "passive"))
      (node (ref "R57") (pin "1") (pinfunction "1_1") (pintype "passive"))
      (node (ref "R58") (pin "2") (pinfunction "2_2") (pintype "passive"))
      (node (ref "R60") (pin "1") (pinfunction "1_1") (pintype "passive"))
    )
    (net (code "60") (name "VCC3P3") (class "Default")
      (node (ref "C125") (pin "1") (pinfunction "1_1") (pintype "passive"))
      (node (ref "C142") (pin "2") (pinfunction "2_2") (pintype "passive"))
      (node (ref "C143") (pin "2") (pinfunction "2_2") (pintype "passive"))
      (node (ref "C144") (pin "2") (pinfunction "2_2") (pintype "passive"))
      (node (ref "C145") (pin "2") (pinfunction "2_2") (pintype "passive"))
      (node (ref "C146") (pin "1") (pinfunction "1_1") (pintype "passive"))
      (node (ref "C147") (pin "1") (pinfunction "1_1") (pintype "passive"))
      (node (ref "C148") (pin "1") (pinfunction "1_1") (pintype "passive"))
      (node (ref "C167") (pin "1") (pinfunction "1_1") (pintype "passive"))
      (node (ref "C168") (pin "1") (pinfunction "1_1") (pintype "passive"))
      (node (ref "C169") (pin "1") (pinfunction "1_1") (pintype "passive"))
      (node (ref "C170") (pin "1") (pinfunction "1_1") (pintype "passive"))
      (node (ref "IC10") (pin "8") (pinfunction "VCC_8") (pintype "passive"))
      (node (ref "IC8") (pin "D4") (pinfunction "VCCIO1_D4") (pintype "power_in"))
      (node (ref "IC8") (pin "F4") (pinfunction "VCCIO1_F4") (pintype "power_in"))
      (node (ref "IC8") (pin "H4") (pinfunction "VCCIO1_H4") (pintype "power_in"))
      (node (ref "IC8") (pin "K4") (pinfunction "VCCIO1_K4") (pintype "power_in"))
      (node (ref "IC9") (pin "16") (pinfunction "V+_16") (pintype "passive"))
      (node (ref "J13") (pin "2") (pinfunction "2_2") (pintype "passive"))
      (node (ref "J14") (pin "2") (pinfunction "2_2") (pintype "passive"))
      (node (ref "R61") (pin "1") (pinfunction "1_1") (pintype "passive"))
      (node (ref "R66") (pin "1") (pinfunction "1_1") (pintype "passive"))
      (node (ref "R70") (pin "1") (pinfunction "1_1") (pintype "passive"))
      (node (ref "R71") (pin "1") (pinfunction "1_1") (pintype "passive"))
      (node (ref "R73") (pin "1") (pinfunction "1_1") (pintype "passive"))
    )
    (net (code "61") (name "VCC_INT") (class "Default")
      (node (ref "R63") (pin "1") (pinfunction "1_1") (pintype "passive"))
    )
    (net (code "62") (name "VDIO_LMS_FPGA") (class "Default")
      (node (ref "C137") (pin "2") (pinfunction "2_2") (pintype "passive"))
      (node (ref "C138") (pin "2") (pinfunction "2_2") (pintype "passive"))
      (node (ref "C139") (pin "2") (pinfunction "2_2") (pintype "passive"))
      (node (ref "C140") (pin "2") (pinfunction "2_2") (pintype "passive"))
      (node (ref "C141") (pin "1") (pinfunction "1_1") (pintype "passive"))
      (node (ref "C153") (pin "1") (pinfunction "1_1") (pintype "passive"))
      (node (ref "C154") (pin "1") (pinfunction "1_1") (pintype "passive"))
      (node (ref "C155") (pin "1") (pinfunction "1_1") (pintype "passive"))
      (node (ref "C156") (pin "1") (pinfunction "1_1") (pintype "passive"))
      (node (ref "C157") (pin "1") (pinfunction "1_1") (pintype "passive"))
      (node (ref "C158") (pin "1") (pinfunction "1_1") (pintype "passive"))
      (node (ref "C159") (pin "1") (pinfunction "1_1") (pintype "passive"))
      (node (ref "C160") (pin "1") (pinfunction "1_1") (pintype "passive"))
      (node (ref "C161") (pin "1") (pinfunction "1_1") (pintype "passive"))
      (node (ref "C162") (pin "1") (pinfunction "1_1") (pintype "passive"))
      (node (ref "C163") (pin "1") (pinfunction "1_1") (pintype "passive"))
      (node (ref "C164") (pin "1") (pinfunction "1_1") (pintype "passive"))
      (node (ref "C165") (pin "1") (pinfunction "1_1") (pintype "passive"))
      (node (ref "C166") (pin "1") (pinfunction "1_1") (pintype "passive"))
      (node (ref "IC8") (pin "A2") (pinfunction "VCCIO8_A2") (pintype "power_in"))
      (node (ref "IC8") (pin "A21") (pinfunction "VCCIO7_A21") (pintype "power_in"))
      (node (ref "IC8") (pin "D11") (pinfunction "VCCIO8_D11") (pintype "power_in"))
      (node (ref "IC8") (pin "D12") (pinfunction "VCCIO7_D12") (pintype "power_in"))
      (node (ref "IC8") (pin "D14") (pinfunction "VCCIO7_D14") (pintype "power_in"))
      (node (ref "IC8") (pin "D16") (pinfunction "VCCIO7_D16") (pintype "power_in"))
      (node (ref "IC8") (pin "D18") (pinfunction "VCCIO7_D18") (pintype "power_in"))
      (node (ref "IC8") (pin "D5") (pinfunction "VCCIO8_D5") (pintype "power_in"))
      (node (ref "IC8") (pin "D9") (pinfunction "VCCIO8_D9") (pintype "power_in"))
      (node (ref "IC8") (pin "E19") (pinfunction "VCCIO6_E19") (pintype "power_in"))
      (node (ref "IC8") (pin "E8") (pinfunction "VCCIO8_E8") (pintype "power_in"))
      (node (ref "IC8") (pin "G19") (pinfunction "VCCIO6_G19") (pintype "power_in"))
      (node (ref "IC8") (pin "J20") (pinfunction "VCCIO6_J20") (pintype "power_in"))
      (node (ref "IC8") (pin "L19") (pinfunction "VCCIO6_L19") (pintype "power_in"))
    )
    (net (code "63") (name "unconnected-(J11-Pad6)") (class "Default")
      (node (ref "J11") (pin "6") (pinfunction "6_6") (pintype "passive+no_connect"))
    )
    (net (code "64") (name "unconnected-(J11-Pad7)") (class "Default")
      (node (ref "J11") (pin "7") (pinfunction "7_7") (pintype "passive+no_connect"))
    )
    (net (code "65") (name "unconnected-(J11-Pad8)") (class "Default")
      (node (ref "J11") (pin "8") (pinfunction "8_8") (pintype "passive+no_connect"))
    )
  )
)
